# Lineboard.net
KiCad netlist of a schematic drawn in EAGLE
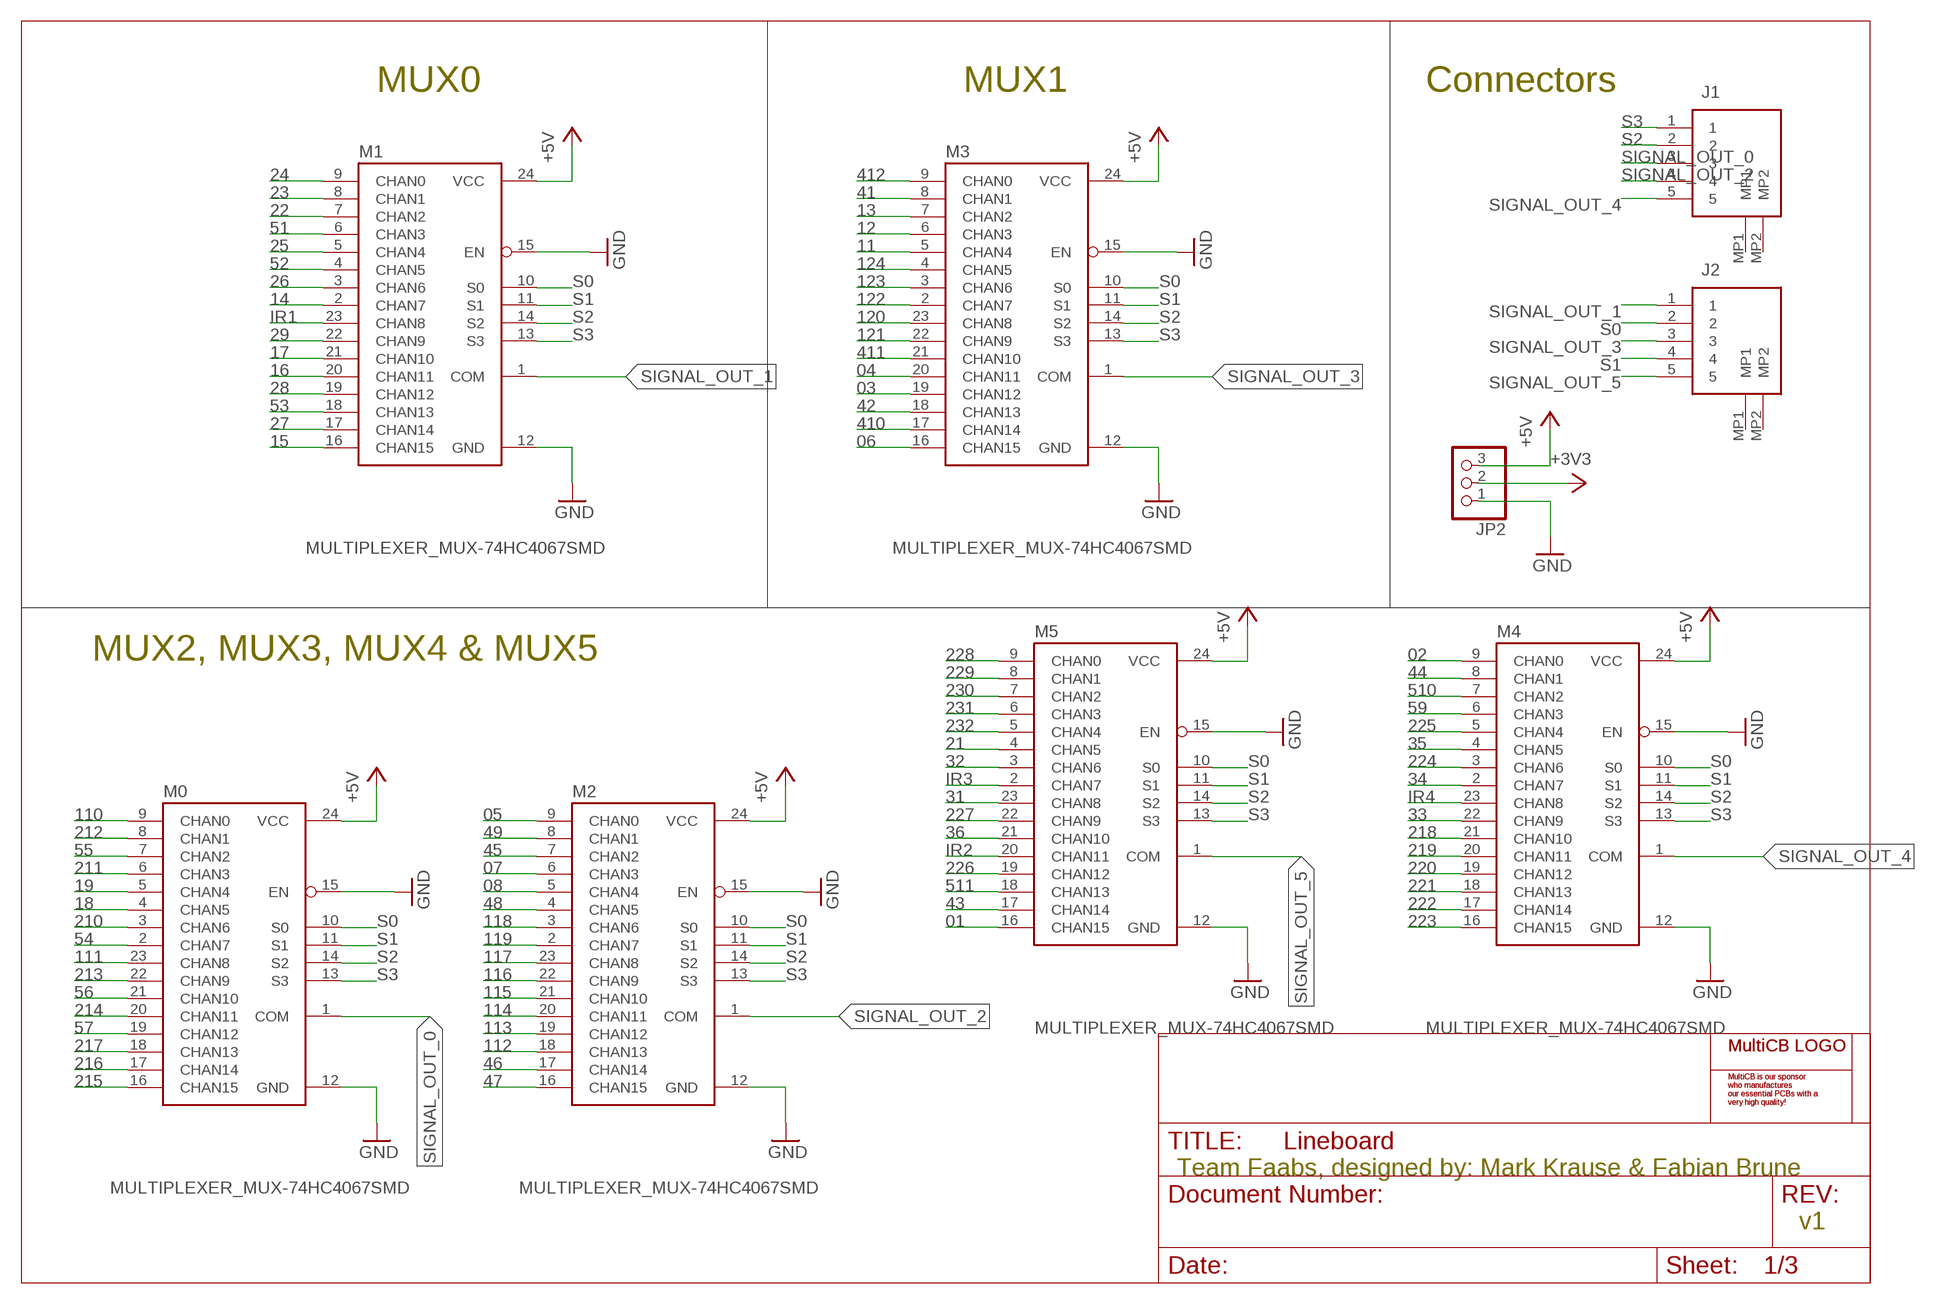
[diagram p0: schematic, sheet 1]
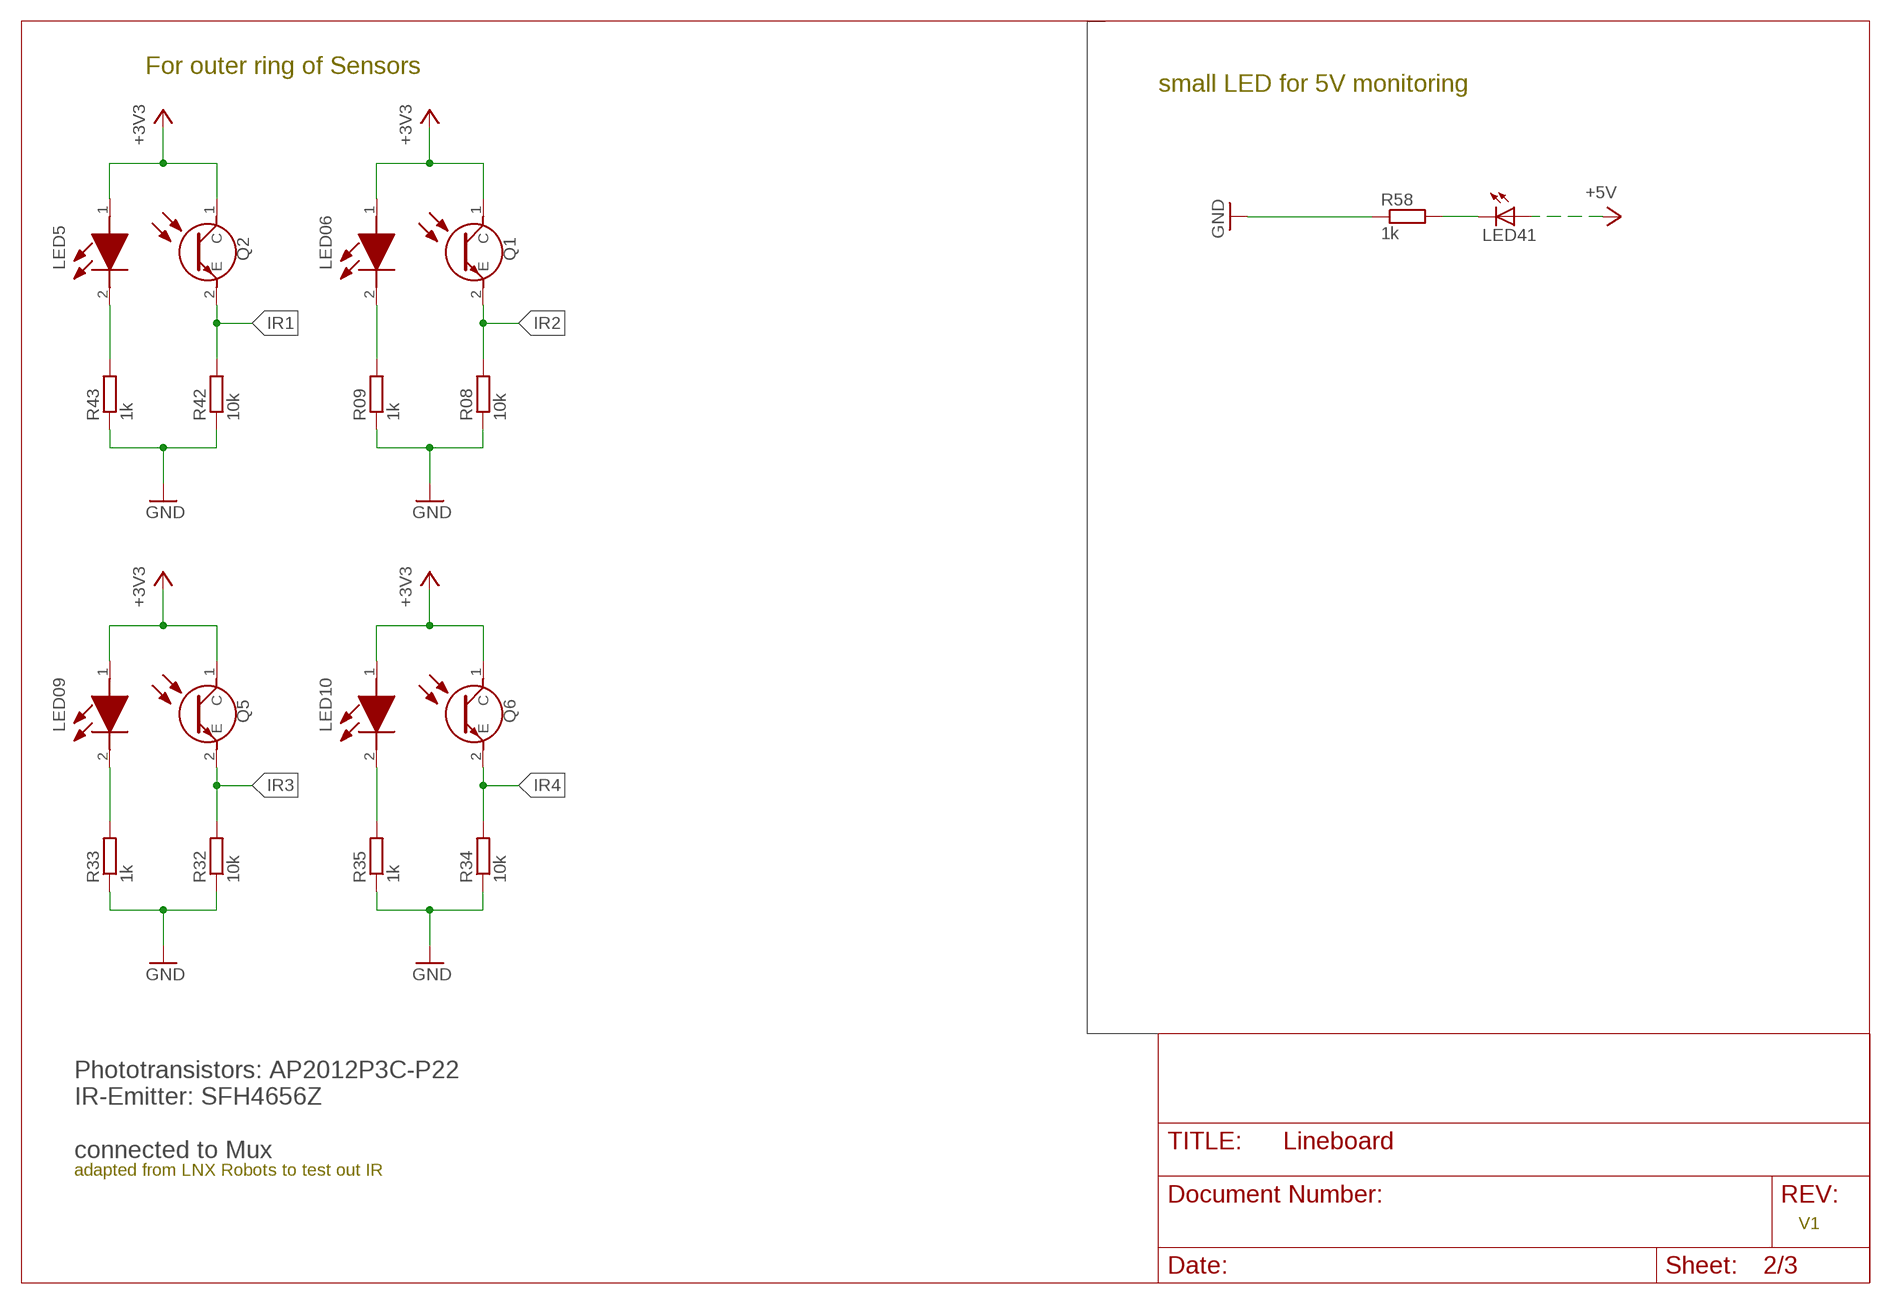
[diagram p1: schematic, sheet 2]
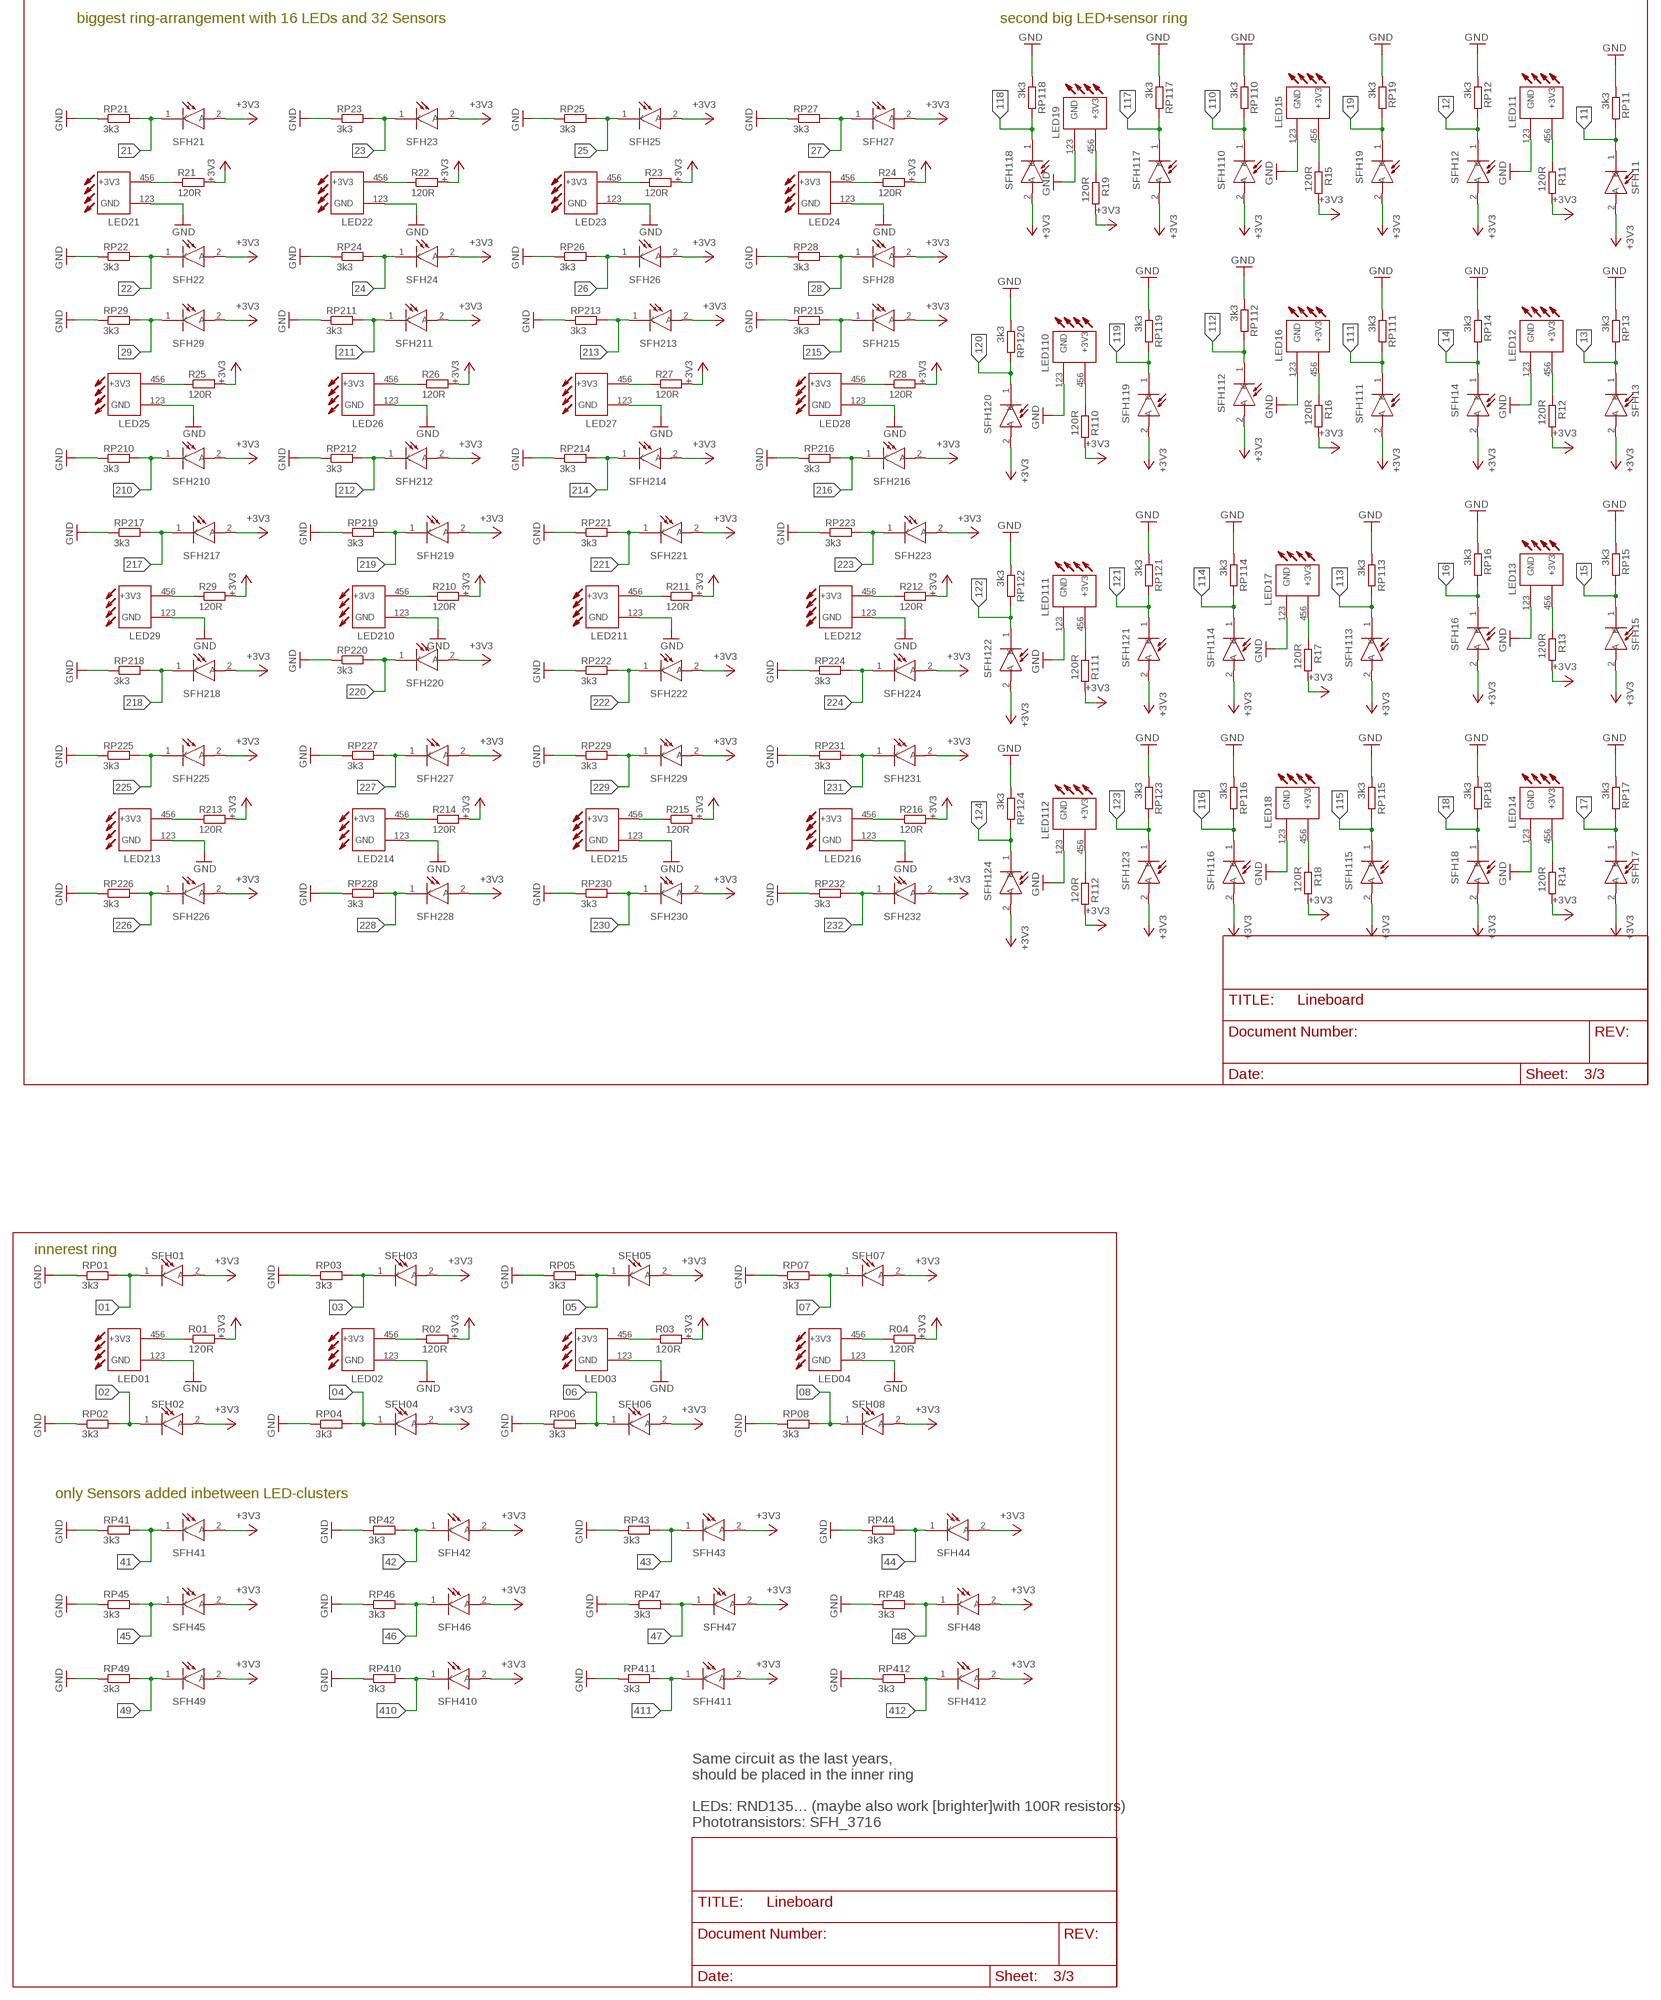
[diagram p2: schematic, sheet 3, part 1 of 2]
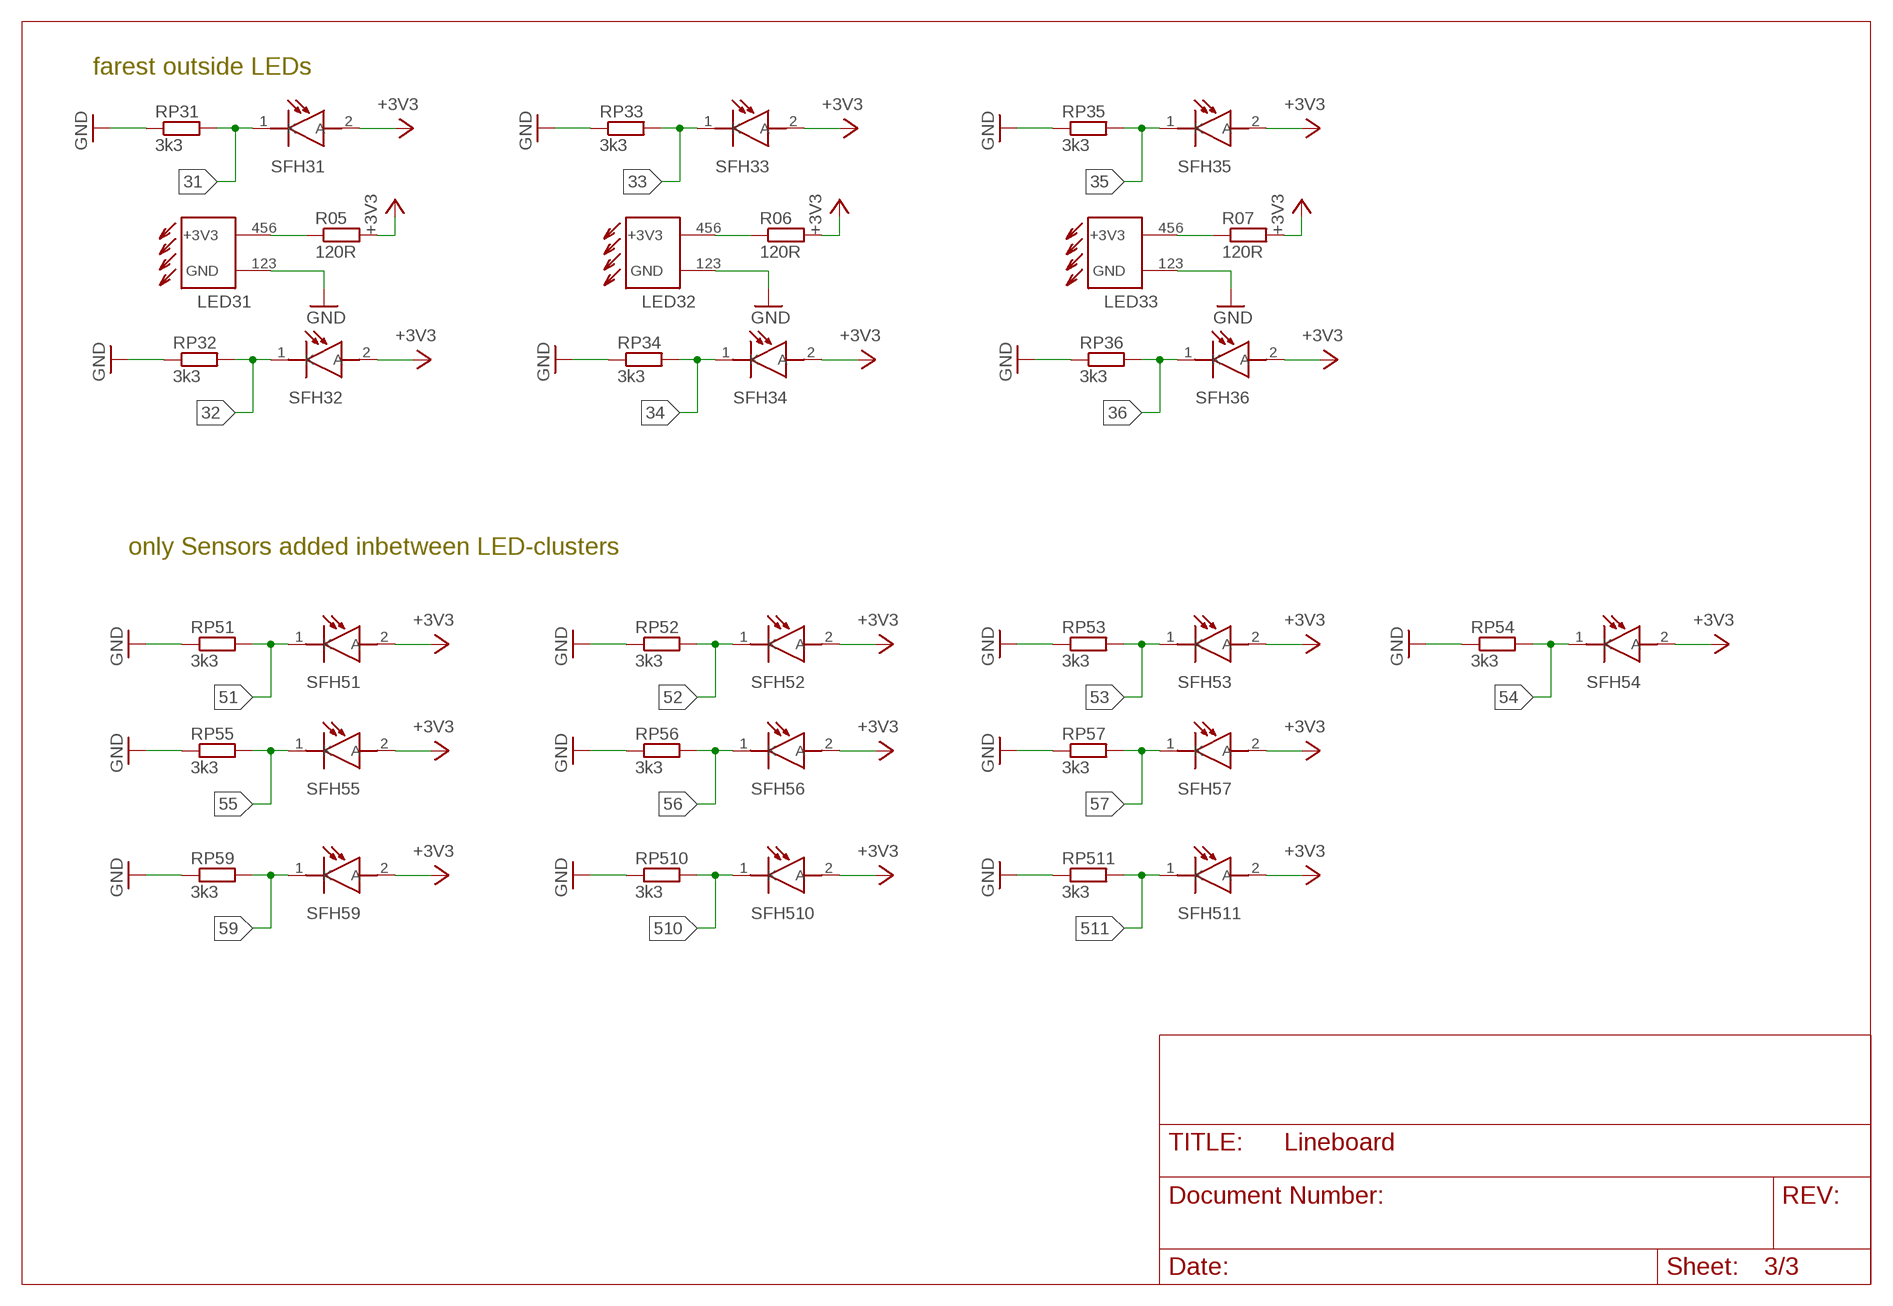
[diagram p3: schematic, sheet 3, part 2 of 2]

(export (version "E")
  (design (tool "Eeschema 10.0.6"))
  (components
    (comp (ref "J1")
      (value "5PIN_1MM_CON")
      (footprint "eagle-import:2035600503")
      (fields
        (field (name "MANUFACTURER_PART_NUMBER") "203560-0503")
        (field (name "MOUSER_PART_NUMBER") "538-203560-0503")
      )
      (libsource (lib "eagle-import") (part "5PIN_1MM_CON"))
    )
    (comp (ref "J2")
      (value "5PIN_1MM_CON")
      (footprint "eagle-import:2035600503")
      (fields
        (field (name "MANUFACTURER_PART_NUMBER") "203560-0503")
        (field (name "MOUSER_PART_NUMBER") "538-203560-0503")
      )
      (libsource (lib "eagle-import") (part "5PIN_1MM_CON"))
    )
    (comp (ref "JP2")
      (value "PINHD-1X3")
      (footprint "eagle-import:1X03")
      (libsource (lib "eagle-import") (part "PINHD-1X3"))
    )
    (comp (ref "M0")
      (value "MULTIPLEXER_MUX-74HC4067SMD")
      (footprint "eagle-import:SPARKFUN_SSOP24")
      (libsource (lib "eagle-import") (part "MULTIPLEXER_MUX-74HC4067SMD"))
    )
    (comp (ref "M1")
      (value "MULTIPLEXER_MUX-74HC4067SMD")
      (footprint "eagle-import:SPARKFUN_SSOP24")
      (libsource (lib "eagle-import") (part "MULTIPLEXER_MUX-74HC4067SMD"))
    )
    (comp (ref "M2")
      (value "MULTIPLEXER_MUX-74HC4067SMD")
      (footprint "eagle-import:SPARKFUN_SSOP24")
      (libsource (lib "eagle-import") (part "MULTIPLEXER_MUX-74HC4067SMD"))
    )
    (comp (ref "M3")
      (value "MULTIPLEXER_MUX-74HC4067SMD")
      (footprint "eagle-import:SPARKFUN_SSOP24")
      (libsource (lib "eagle-import") (part "MULTIPLEXER_MUX-74HC4067SMD"))
    )
    (comp (ref "M4")
      (value "MULTIPLEXER_MUX-74HC4067SMD")
      (footprint "eagle-import:SPARKFUN_SSOP24")
      (libsource (lib "eagle-import") (part "MULTIPLEXER_MUX-74HC4067SMD"))
    )
    (comp (ref "M5")
      (value "MULTIPLEXER_MUX-74HC4067SMD")
      (footprint "eagle-import:SPARKFUN_SSOP24")
      (libsource (lib "eagle-import") (part "MULTIPLEXER_MUX-74HC4067SMD"))
    )
    (comp (ref "U$1")
      (value "MULTICB_LOGOSTANDART")
      (footprint "eagle-import:SMALL_STANDARTLOGO_28MM")
      (libsource (lib "eagle-import") (part "MULTICB_LOGOSTANDART"))
    )
    (comp (ref "U$5")
      (value "MULTICB_LOGOSTANDART")
      (footprint "eagle-import:SMALL_STANDARTLOGO_28MM")
      (libsource (lib "eagle-import") (part "MULTICB_LOGOSTANDART"))
    )
    (comp (ref "LED01")
      (value "RND135-00056LEDD")
      (footprint "eagle-import:LED")
      (libsource (lib "eagle-import") (part "RND135-00056LEDD"))
    )
    (comp (ref "LED02")
      (value "RND135-00056LEDD")
      (footprint "eagle-import:LED")
      (libsource (lib "eagle-import") (part "RND135-00056LEDD"))
    )
    (comp (ref "LED03")
      (value "RND135-00056LEDD")
      (footprint "eagle-import:LED")
      (libsource (lib "eagle-import") (part "RND135-00056LEDD"))
    )
    (comp (ref "LED04")
      (value "RND135-00056LEDD")
      (footprint "eagle-import:LED")
      (libsource (lib "eagle-import") (part "RND135-00056LEDD"))
    )
    (comp (ref "LED11")
      (value "RND135-00056LEDD")
      (footprint "eagle-import:LED")
      (libsource (lib "eagle-import") (part "RND135-00056LEDD"))
    )
    (comp (ref "LED12")
      (value "RND135-00056LEDD")
      (footprint "eagle-import:LED")
      (libsource (lib "eagle-import") (part "RND135-00056LEDD"))
    )
    (comp (ref "LED13")
      (value "RND135-00056LEDD")
      (footprint "eagle-import:LED")
      (libsource (lib "eagle-import") (part "RND135-00056LEDD"))
    )
    (comp (ref "LED14")
      (value "RND135-00056LEDD")
      (footprint "eagle-import:LED")
      (libsource (lib "eagle-import") (part "RND135-00056LEDD"))
    )
    (comp (ref "LED15")
      (value "RND135-00056LEDD")
      (footprint "eagle-import:LED")
      (libsource (lib "eagle-import") (part "RND135-00056LEDD"))
    )
    (comp (ref "LED16")
      (value "RND135-00056LEDD")
      (footprint "eagle-import:LED")
      (libsource (lib "eagle-import") (part "RND135-00056LEDD"))
    )
    (comp (ref "LED17")
      (value "RND135-00056LEDD")
      (footprint "eagle-import:LED")
      (libsource (lib "eagle-import") (part "RND135-00056LEDD"))
    )
    (comp (ref "LED18")
      (value "RND135-00056LEDD")
      (footprint "eagle-import:LED")
      (libsource (lib "eagle-import") (part "RND135-00056LEDD"))
    )
    (comp (ref "LED19")
      (value "RND135-00056LEDD")
      (footprint "eagle-import:LED")
      (libsource (lib "eagle-import") (part "RND135-00056LEDD"))
    )
    (comp (ref "LED21")
      (value "RND135-00056LEDD")
      (footprint "eagle-import:LED")
      (libsource (lib "eagle-import") (part "RND135-00056LEDD"))
    )
    (comp (ref "LED22")
      (value "RND135-00056LEDD")
      (footprint "eagle-import:LED")
      (libsource (lib "eagle-import") (part "RND135-00056LEDD"))
    )
    (comp (ref "LED23")
      (value "RND135-00056LEDD")
      (footprint "eagle-import:LED")
      (libsource (lib "eagle-import") (part "RND135-00056LEDD"))
    )
    (comp (ref "LED24")
      (value "RND135-00056LEDD")
      (footprint "eagle-import:LED")
      (libsource (lib "eagle-import") (part "RND135-00056LEDD"))
    )
    (comp (ref "LED25")
      (value "RND135-00056LEDD")
      (footprint "eagle-import:LED")
      (libsource (lib "eagle-import") (part "RND135-00056LEDD"))
    )
    (comp (ref "LED26")
      (value "RND135-00056LEDD")
      (footprint "eagle-import:LED")
      (libsource (lib "eagle-import") (part "RND135-00056LEDD"))
    )
    (comp (ref "LED27")
      (value "RND135-00056LEDD")
      (footprint "eagle-import:LED")
      (libsource (lib "eagle-import") (part "RND135-00056LEDD"))
    )
    (comp (ref "LED28")
      (value "RND135-00056LEDD")
      (footprint "eagle-import:LED")
      (libsource (lib "eagle-import") (part "RND135-00056LEDD"))
    )
    (comp (ref "LED29")
      (value "RND135-00056LEDD")
      (footprint "eagle-import:LED")
      (libsource (lib "eagle-import") (part "RND135-00056LEDD"))
    )
    (comp (ref "LED31")
      (value "RND135-00056LEDD")
      (footprint "eagle-import:LED")
      (libsource (lib "eagle-import") (part "RND135-00056LEDD"))
    )
    (comp (ref "LED32")
      (value "RND135-00056LEDD")
      (footprint "eagle-import:LED")
      (libsource (lib "eagle-import") (part "RND135-00056LEDD"))
    )
    (comp (ref "LED33")
      (value "RND135-00056LEDD")
      (footprint "eagle-import:LED")
      (libsource (lib "eagle-import") (part "RND135-00056LEDD"))
    )
    (comp (ref "LED110")
      (value "RND135-00056LEDD")
      (footprint "eagle-import:LED")
      (libsource (lib "eagle-import") (part "RND135-00056LEDD"))
    )
    (comp (ref "LED111")
      (value "RND135-00056LEDD")
      (footprint "eagle-import:LED")
      (libsource (lib "eagle-import") (part "RND135-00056LEDD"))
    )
    (comp (ref "LED112")
      (value "RND135-00056LEDD")
      (footprint "eagle-import:LED")
      (libsource (lib "eagle-import") (part "RND135-00056LEDD"))
    )
    (comp (ref "LED210")
      (value "RND135-00056LEDD")
      (footprint "eagle-import:LED")
      (libsource (lib "eagle-import") (part "RND135-00056LEDD"))
    )
    (comp (ref "LED211")
      (value "RND135-00056LEDD")
      (footprint "eagle-import:LED")
      (libsource (lib "eagle-import") (part "RND135-00056LEDD"))
    )
    (comp (ref "LED212")
      (value "RND135-00056LEDD")
      (footprint "eagle-import:LED")
      (libsource (lib "eagle-import") (part "RND135-00056LEDD"))
    )
    (comp (ref "LED213")
      (value "RND135-00056LEDD")
      (footprint "eagle-import:LED")
      (libsource (lib "eagle-import") (part "RND135-00056LEDD"))
    )
    (comp (ref "LED214")
      (value "RND135-00056LEDD")
      (footprint "eagle-import:LED")
      (libsource (lib "eagle-import") (part "RND135-00056LEDD"))
    )
    (comp (ref "LED215")
      (value "RND135-00056LEDD")
      (footprint "eagle-import:LED")
      (libsource (lib "eagle-import") (part "RND135-00056LEDD"))
    )
    (comp (ref "LED216")
      (value "RND135-00056LEDD")
      (footprint "eagle-import:LED")
      (libsource (lib "eagle-import") (part "RND135-00056LEDD"))
    )
    (comp (ref "R01")
      (value "120R")
      (footprint "eagle-import:R0603")
      (libsource (lib "eagle-import") (part "R-EU_R0603"))
    )
    (comp (ref "R02")
      (value "120R")
      (footprint "eagle-import:R0603")
      (libsource (lib "eagle-import") (part "R-EU_R0603"))
    )
    (comp (ref "R03")
      (value "120R")
      (footprint "eagle-import:R0603")
      (libsource (lib "eagle-import") (part "R-EU_R0603"))
    )
    (comp (ref "R04")
      (value "120R")
      (footprint "eagle-import:R0603")
      (libsource (lib "eagle-import") (part "R-EU_R0603"))
    )
    (comp (ref "R05")
      (value "120R")
      (footprint "eagle-import:R0603")
      (libsource (lib "eagle-import") (part "R-EU_R0603"))
    )
    (comp (ref "R06")
      (value "120R")
      (footprint "eagle-import:R0603")
      (libsource (lib "eagle-import") (part "R-EU_R0603"))
    )
    (comp (ref "R07")
      (value "120R")
      (footprint "eagle-import:R0603")
      (libsource (lib "eagle-import") (part "R-EU_R0603"))
    )
    (comp (ref "R11")
      (value "120R")
      (footprint "eagle-import:R0603")
      (libsource (lib "eagle-import") (part "R-EU_R0603"))
    )
    (comp (ref "R12")
      (value "120R")
      (footprint "eagle-import:R0603")
      (libsource (lib "eagle-import") (part "R-EU_R0603"))
    )
    (comp (ref "R13")
      (value "120R")
      (footprint "eagle-import:R0603")
      (libsource (lib "eagle-import") (part "R-EU_R0603"))
    )
    (comp (ref "R14")
      (value "120R")
      (footprint "eagle-import:R0603")
      (libsource (lib "eagle-import") (part "R-EU_R0603"))
    )
    (comp (ref "R15")
      (value "120R")
      (footprint "eagle-import:R0603")
      (libsource (lib "eagle-import") (part "R-EU_R0603"))
    )
    (comp (ref "R16")
      (value "120R")
      (footprint "eagle-import:R0603")
      (libsource (lib "eagle-import") (part "R-EU_R0603"))
    )
    (comp (ref "R17")
      (value "120R")
      (footprint "eagle-import:R0603")
      (libsource (lib "eagle-import") (part "R-EU_R0603"))
    )
    (comp (ref "R18")
      (value "120R")
      (footprint "eagle-import:R0603")
      (libsource (lib "eagle-import") (part "R-EU_R0603"))
    )
    (comp (ref "R19")
      (value "120R")
      (footprint "eagle-import:R0603")
      (libsource (lib "eagle-import") (part "R-EU_R0603"))
    )
    (comp (ref "R21")
      (value "120R")
      (footprint "eagle-import:R0603")
      (libsource (lib "eagle-import") (part "R-EU_R0603"))
    )
    (comp (ref "R22")
      (value "120R")
      (footprint "eagle-import:R0603")
      (libsource (lib "eagle-import") (part "R-EU_R0603"))
    )
    (comp (ref "R23")
      (value "120R")
      (footprint "eagle-import:R0603")
      (libsource (lib "eagle-import") (part "R-EU_R0603"))
    )
    (comp (ref "R24")
      (value "120R")
      (footprint "eagle-import:R0603")
      (libsource (lib "eagle-import") (part "R-EU_R0603"))
    )
    (comp (ref "R25")
      (value "120R")
      (footprint "eagle-import:R0603")
      (libsource (lib "eagle-import") (part "R-EU_R0603"))
    )
    (comp (ref "R26")
      (value "120R")
      (footprint "eagle-import:R0603")
      (libsource (lib "eagle-import") (part "R-EU_R0603"))
    )
    (comp (ref "R27")
      (value "120R")
      (footprint "eagle-import:R0603")
      (libsource (lib "eagle-import") (part "R-EU_R0603"))
    )
    (comp (ref "R28")
      (value "120R")
      (footprint "eagle-import:R0603")
      (libsource (lib "eagle-import") (part "R-EU_R0603"))
    )
    (comp (ref "R29")
      (value "120R")
      (footprint "eagle-import:R0603")
      (libsource (lib "eagle-import") (part "R-EU_R0603"))
    )
    (comp (ref "R110")
      (value "120R")
      (footprint "eagle-import:R0603")
      (libsource (lib "eagle-import") (part "R-EU_R0603"))
    )
    (comp (ref "R111")
      (value "120R")
      (footprint "eagle-import:R0603")
      (libsource (lib "eagle-import") (part "R-EU_R0603"))
    )
    (comp (ref "R112")
      (value "120R")
      (footprint "eagle-import:R0603")
      (libsource (lib "eagle-import") (part "R-EU_R0603"))
    )
    (comp (ref "R210")
      (value "120R")
      (footprint "eagle-import:R0603")
      (libsource (lib "eagle-import") (part "R-EU_R0603"))
    )
    (comp (ref "R211")
      (value "120R")
      (footprint "eagle-import:R0603")
      (libsource (lib "eagle-import") (part "R-EU_R0603"))
    )
    (comp (ref "R212")
      (value "120R")
      (footprint "eagle-import:R0603")
      (libsource (lib "eagle-import") (part "R-EU_R0603"))
    )
    (comp (ref "R213")
      (value "120R")
      (footprint "eagle-import:R0603")
      (libsource (lib "eagle-import") (part "R-EU_R0603"))
    )
    (comp (ref "R214")
      (value "120R")
      (footprint "eagle-import:R0603")
      (libsource (lib "eagle-import") (part "R-EU_R0603"))
    )
    (comp (ref "R215")
      (value "120R")
      (footprint "eagle-import:R0603")
      (libsource (lib "eagle-import") (part "R-EU_R0603"))
    )
    (comp (ref "R216")
      (value "120R")
      (footprint "eagle-import:R0603")
      (libsource (lib "eagle-import") (part "R-EU_R0603"))
    )
    (comp (ref "RP01")
      (value "3k3")
      (footprint "eagle-import:R0603")
      (libsource (lib "eagle-import") (part "R-EU_R0603"))
    )
    (comp (ref "RP02")
      (value "3k3")
      (footprint "eagle-import:R0603")
      (libsource (lib "eagle-import") (part "R-EU_R0603"))
    )
    (comp (ref "RP03")
      (value "3k3")
      (footprint "eagle-import:R0603")
      (libsource (lib "eagle-import") (part "R-EU_R0603"))
    )
    (comp (ref "RP04")
      (value "3k3")
      (footprint "eagle-import:R0603")
      (libsource (lib "eagle-import") (part "R-EU_R0603"))
    )
    (comp (ref "RP05")
      (value "3k3")
      (footprint "eagle-import:R0603")
      (libsource (lib "eagle-import") (part "R-EU_R0603"))
    )
    (comp (ref "RP06")
      (value "3k3")
      (footprint "eagle-import:R0603")
      (libsource (lib "eagle-import") (part "R-EU_R0603"))
    )
    (comp (ref "RP07")
      (value "3k3")
      (footprint "eagle-import:R0603")
      (libsource (lib "eagle-import") (part "R-EU_R0603"))
    )
    (comp (ref "RP08")
      (value "3k3")
      (footprint "eagle-import:R0603")
      (libsource (lib "eagle-import") (part "R-EU_R0603"))
    )
    (comp (ref "RP11")
      (value "3k3")
      (footprint "eagle-import:R0603")
      (libsource (lib "eagle-import") (part "R-EU_R0603"))
    )
    (comp (ref "RP12")
      (value "3k3")
      (footprint "eagle-import:R0603")
      (libsource (lib "eagle-import") (part "R-EU_R0603"))
    )
    (comp (ref "RP13")
      (value "3k3")
      (footprint "eagle-import:R0603")
      (libsource (lib "eagle-import") (part "R-EU_R0603"))
    )
    (comp (ref "RP14")
      (value "3k3")
      (footprint "eagle-import:R0603")
      (libsource (lib "eagle-import") (part "R-EU_R0603"))
    )
    (comp (ref "RP15")
      (value "3k3")
      (footprint "eagle-import:R0603")
      (libsource (lib "eagle-import") (part "R-EU_R0603"))
    )
    (comp (ref "RP16")
      (value "3k3")
      (footprint "eagle-import:R0603")
      (libsource (lib "eagle-import") (part "R-EU_R0603"))
    )
    (comp (ref "RP17")
      (value "3k3")
      (footprint "eagle-import:R0603")
      (libsource (lib "eagle-import") (part "R-EU_R0603"))
    )
    (comp (ref "RP18")
      (value "3k3")
      (footprint "eagle-import:R0603")
      (libsource (lib "eagle-import") (part "R-EU_R0603"))
    )
    (comp (ref "RP19")
      (value "3k3")
      (footprint "eagle-import:R0603")
      (libsource (lib "eagle-import") (part "R-EU_R0603"))
    )
    (comp (ref "RP21")
      (value "3k3")
      (footprint "eagle-import:R0603")
      (libsource (lib "eagle-import") (part "R-EU_R0603"))
    )
    (comp (ref "RP22")
      (value "3k3")
      (footprint "eagle-import:R0603")
      (libsource (lib "eagle-import") (part "R-EU_R0603"))
    )
    (comp (ref "RP23")
      (value "3k3")
      (footprint "eagle-import:R0603")
      (libsource (lib "eagle-import") (part "R-EU_R0603"))
    )
    (comp (ref "RP24")
      (value "3k3")
      (footprint "eagle-import:R0603")
      (libsource (lib "eagle-import") (part "R-EU_R0603"))
    )
    (comp (ref "RP25")
      (value "3k3")
      (footprint "eagle-import:R0603")
      (libsource (lib "eagle-import") (part "R-EU_R0603"))
    )
    (comp (ref "RP26")
      (value "3k3")
      (footprint "eagle-import:R0603")
      (libsource (lib "eagle-import") (part "R-EU_R0603"))
    )
    (comp (ref "RP27")
      (value "3k3")
      (footprint "eagle-import:R0603")
      (libsource (lib "eagle-import") (part "R-EU_R0603"))
    )
    (comp (ref "RP28")
      (value "3k3")
      (footprint "eagle-import:R0603")
      (libsource (lib "eagle-import") (part "R-EU_R0603"))
    )
    (comp (ref "RP29")
      (value "3k3")
      (footprint "eagle-import:R0603")
      (libsource (lib "eagle-import") (part "R-EU_R0603"))
    )
    (comp (ref "RP31")
      (value "3k3")
      (footprint "eagle-import:R0603")
      (libsource (lib "eagle-import") (part "R-EU_R0603"))
    )
    (comp (ref "RP32")
      (value "3k3")
      (footprint "eagle-import:R0603")
      (libsource (lib "eagle-import") (part "R-EU_R0603"))
    )
    (comp (ref "RP33")
      (value "3k3")
      (footprint "eagle-import:R0603")
      (libsource (lib "eagle-import") (part "R-EU_R0603"))
    )
    (comp (ref "RP34")
      (value "3k3")
      (footprint "eagle-import:R0603")
      (libsource (lib "eagle-import") (part "R-EU_R0603"))
    )
    (comp (ref "RP35")
      (value "3k3")
      (footprint "eagle-import:R0603")
      (libsource (lib "eagle-import") (part "R-EU_R0603"))
    )
    (comp (ref "RP36")
      (value "3k3")
      (footprint "eagle-import:R0603")
      (libsource (lib "eagle-import") (part "R-EU_R0603"))
    )
    (comp (ref "RP41")
      (value "3k3")
      (footprint "eagle-import:R0603")
      (libsource (lib "eagle-import") (part "R-EU_R0603"))
    )
    (comp (ref "RP42")
      (value "3k3")
      (footprint "eagle-import:R0603")
      (libsource (lib "eagle-import") (part "R-EU_R0603"))
    )
    (comp (ref "RP43")
      (value "3k3")
      (footprint "eagle-import:R0603")
      (libsource (lib "eagle-import") (part "R-EU_R0603"))
    )
    (comp (ref "RP44")
      (value "3k3")
      (footprint "eagle-import:R0603")
      (libsource (lib "eagle-import") (part "R-EU_R0603"))
    )
    (comp (ref "RP45")
      (value "3k3")
      (footprint "eagle-import:R0603")
      (libsource (lib "eagle-import") (part "R-EU_R0603"))
    )
    (comp (ref "RP46")
      (value "3k3")
      (footprint "eagle-import:R0603")
      (libsource (lib "eagle-import") (part "R-EU_R0603"))
    )
    (comp (ref "RP47")
      (value "3k3")
      (footprint "eagle-import:R0603")
      (libsource (lib "eagle-import") (part "R-EU_R0603"))
    )
    (comp (ref "RP48")
      (value "3k3")
      (footprint "eagle-import:R0603")
      (libsource (lib "eagle-import") (part "R-EU_R0603"))
    )
    (comp (ref "RP49")
      (value "3k3")
      (footprint "eagle-import:R0603")
      (libsource (lib "eagle-import") (part "R-EU_R0603"))
    )
    (comp (ref "RP51")
      (value "3k3")
      (footprint "eagle-import:R0603")
      (libsource (lib "eagle-import") (part "R-EU_R0603"))
    )
    (comp (ref "RP52")
      (value "3k3")
      (footprint "eagle-import:R0603")
      (libsource (lib "eagle-import") (part "R-EU_R0603"))
    )
    (comp (ref "RP53")
      (value "3k3")
      (footprint "eagle-import:R0603")
      (libsource (lib "eagle-import") (part "R-EU_R0603"))
    )
    (comp (ref "RP54")
      (value "3k3")
      (footprint "eagle-import:R0603")
      (libsource (lib "eagle-import") (part "R-EU_R0603"))
    )
    (comp (ref "RP55")
      (value "3k3")
      (footprint "eagle-import:R0603")
      (libsource (lib "eagle-import") (part "R-EU_R0603"))
    )
    (comp (ref "RP56")
      (value "3k3")
      (footprint "eagle-import:R0603")
      (libsource (lib "eagle-import") (part "R-EU_R0603"))
    )
    (comp (ref "RP57")
      (value "3k3")
      (footprint "eagle-import:R0603")
      (libsource (lib "eagle-import") (part "R-EU_R0603"))
    )
    (comp (ref "RP59")
      (value "3k3")
      (footprint "eagle-import:R0603")
      (libsource (lib "eagle-import") (part "R-EU_R0603"))
    )
    (comp (ref "RP110")
      (value "3k3")
      (footprint "eagle-import:R0603")
      (libsource (lib "eagle-import") (part "R-EU_R0603"))
    )
    (comp (ref "RP111")
      (value "3k3")
      (footprint "eagle-import:R0603")
      (libsource (lib "eagle-import") (part "R-EU_R0603"))
    )
    (comp (ref "RP112")
      (value "3k3")
      (footprint "eagle-import:R0603")
      (libsource (lib "eagle-import") (part "R-EU_R0603"))
    )
    (comp (ref "RP113")
      (value "3k3")
      (footprint "eagle-import:R0603")
      (libsource (lib "eagle-import") (part "R-EU_R0603"))
    )
    (comp (ref "RP114")
      (value "3k3")
      (footprint "eagle-import:R0603")
      (libsource (lib "eagle-import") (part "R-EU_R0603"))
    )
    (comp (ref "RP115")
      (value "3k3")
      (footprint "eagle-import:R0603")
      (libsource (lib "eagle-import") (part "R-EU_R0603"))
    )
    (comp (ref "RP116")
      (value "3k3")
      (footprint "eagle-import:R0603")
      (libsource (lib "eagle-import") (part "R-EU_R0603"))
    )
    (comp (ref "RP117")
      (value "3k3")
      (footprint "eagle-import:R0603")
      (libsource (lib "eagle-import") (part "R-EU_R0603"))
    )
    (comp (ref "RP118")
      (value "3k3")
      (footprint "eagle-import:R0603")
      (libsource (lib "eagle-import") (part "R-EU_R0603"))
    )
    (comp (ref "RP119")
      (value "3k3")
      (footprint "eagle-import:R0603")
      (libsource (lib "eagle-import") (part "R-EU_R0603"))
    )
    (comp (ref "RP120")
      (value "3k3")
      (footprint "eagle-import:R0603")
      (libsource (lib "eagle-import") (part "R-EU_R0603"))
    )
    (comp (ref "RP121")
      (value "3k3")
      (footprint "eagle-import:R0603")
      (libsource (lib "eagle-import") (part "R-EU_R0603"))
    )
    (comp (ref "RP122")
      (value "3k3")
      (footprint "eagle-import:R0603")
      (libsource (lib "eagle-import") (part "R-EU_R0603"))
    )
    (comp (ref "RP123")
      (value "3k3")
      (footprint "eagle-import:R0603")
      (libsource (lib "eagle-import") (part "R-EU_R0603"))
    )
    (comp (ref "RP124")
      (value "3k3")
      (footprint "eagle-import:R0603")
      (libsource (lib "eagle-import") (part "R-EU_R0603"))
    )
    (comp (ref "RP210")
      (value "3k3")
      (footprint "eagle-import:R0603")
      (libsource (lib "eagle-import") (part "R-EU_R0603"))
    )
    (comp (ref "RP211")
      (value "3k3")
      (footprint "eagle-import:R0603")
      (libsource (lib "eagle-import") (part "R-EU_R0603"))
    )
    (comp (ref "RP212")
      (value "3k3")
      (footprint "eagle-import:R0603")
      (libsource (lib "eagle-import") (part "R-EU_R0603"))
    )
    (comp (ref "RP213")
      (value "3k3")
      (footprint "eagle-import:R0603")
      (libsource (lib "eagle-import") (part "R-EU_R0603"))
    )
    (comp (ref "RP214")
      (value "3k3")
      (footprint "eagle-import:R0603")
      (libsource (lib "eagle-import") (part "R-EU_R0603"))
    )
    (comp (ref "RP215")
      (value "3k3")
      (footprint "eagle-import:R0603")
      (libsource (lib "eagle-import") (part "R-EU_R0603"))
    )
    (comp (ref "RP216")
      (value "3k3")
      (footprint "eagle-import:R0603")
      (libsource (lib "eagle-import") (part "R-EU_R0603"))
    )
    (comp (ref "RP217")
      (value "3k3")
      (footprint "eagle-import:R0603")
      (libsource (lib "eagle-import") (part "R-EU_R0603"))
    )
    (comp (ref "RP218")
      (value "3k3")
      (footprint "eagle-import:R0603")
      (libsource (lib "eagle-import") (part "R-EU_R0603"))
    )
    (comp (ref "RP219")
      (value "3k3")
      (footprint "eagle-import:R0603")
      (libsource (lib "eagle-import") (part "R-EU_R0603"))
    )
    (comp (ref "RP220")
      (value "3k3")
      (footprint "eagle-import:R0603")
      (libsource (lib "eagle-import") (part "R-EU_R0603"))
    )
    (comp (ref "RP221")
      (value "3k3")
      (footprint "eagle-import:R0603")
      (libsource (lib "eagle-import") (part "R-EU_R0603"))
    )
    (comp (ref "RP222")
      (value "3k3")
      (footprint "eagle-import:R0603")
      (libsource (lib "eagle-import") (part "R-EU_R0603"))
    )
    (comp (ref "RP223")
      (value "3k3")
      (footprint "eagle-import:R0603")
      (libsource (lib "eagle-import") (part "R-EU_R0603"))
    )
    (comp (ref "RP224")
      (value "3k3")
      (footprint "eagle-import:R0603")
      (libsource (lib "eagle-import") (part "R-EU_R0603"))
    )
    (comp (ref "RP225")
      (value "3k3")
      (footprint "eagle-import:R0603")
      (libsource (lib "eagle-import") (part "R-EU_R0603"))
    )
    (comp (ref "RP226")
      (value "3k3")
      (footprint "eagle-import:R0603")
      (libsource (lib "eagle-import") (part "R-EU_R0603"))
    )
    (comp (ref "RP227")
      (value "3k3")
      (footprint "eagle-import:R0603")
      (libsource (lib "eagle-import") (part "R-EU_R0603"))
    )
    (comp (ref "RP228")
      (value "3k3")
      (footprint "eagle-import:R0603")
      (libsource (lib "eagle-import") (part "R-EU_R0603"))
    )
    (comp (ref "RP229")
      (value "3k3")
      (footprint "eagle-import:R0603")
      (libsource (lib "eagle-import") (part "R-EU_R0603"))
    )
    (comp (ref "RP230")
      (value "3k3")
      (footprint "eagle-import:R0603")
      (libsource (lib "eagle-import") (part "R-EU_R0603"))
    )
    (comp (ref "RP231")
      (value "3k3")
      (footprint "eagle-import:R0603")
      (libsource (lib "eagle-import") (part "R-EU_R0603"))
    )
    (comp (ref "RP232")
      (value "3k3")
      (footprint "eagle-import:R0603")
      (libsource (lib "eagle-import") (part "R-EU_R0603"))
    )
    (comp (ref "RP410")
      (value "3k3")
      (footprint "eagle-import:R0603")
      (libsource (lib "eagle-import") (part "R-EU_R0603"))
    )
    (comp (ref "RP411")
      (value "3k3")
      (footprint "eagle-import:R0603")
      (libsource (lib "eagle-import") (part "R-EU_R0603"))
    )
    (comp (ref "RP412")
      (value "3k3")
      (footprint "eagle-import:R0603")
      (libsource (lib "eagle-import") (part "R-EU_R0603"))
    )
    (comp (ref "RP510")
      (value "3k3")
      (footprint "eagle-import:R0603")
      (libsource (lib "eagle-import") (part "R-EU_R0603"))
    )
    (comp (ref "RP511")
      (value "3k3")
      (footprint "eagle-import:R0603")
      (libsource (lib "eagle-import") (part "R-EU_R0603"))
    )
    (comp (ref "SFH01")
      (value "SFH_3716")
      (footprint "eagle-import:LEDC2012X89N")
      (fields
        (field (name "MANUFACTURER_PART_NUMBER") "SFH 3716")
        (field (name "MOUSER_PART_NUMBER") "720-SFH3716")
        (field (name "RS_PART_NUMBER") "1115952P")
      )
      (libsource (lib "eagle-import") (part "SFH_3716"))
    )
    (comp (ref "SFH02")
      (value "SFH_3716")
      (footprint "eagle-import:LEDC2012X89N")
      (fields
        (field (name "MANUFACTURER_PART_NUMBER") "SFH 3716")
        (field (name "MOUSER_PART_NUMBER") "720-SFH3716")
        (field (name "RS_PART_NUMBER") "1115952P")
      )
      (libsource (lib "eagle-import") (part "SFH_3716"))
    )
    (comp (ref "SFH03")
      (value "SFH_3716")
      (footprint "eagle-import:LEDC2012X89N")
      (fields
        (field (name "MANUFACTURER_PART_NUMBER") "SFH 3716")
        (field (name "MOUSER_PART_NUMBER") "720-SFH3716")
        (field (name "RS_PART_NUMBER") "1115952P")
      )
      (libsource (lib "eagle-import") (part "SFH_3716"))
    )
    (comp (ref "SFH04")
      (value "SFH_3716")
      (footprint "eagle-import:LEDC2012X89N")
      (fields
        (field (name "MANUFACTURER_PART_NUMBER") "SFH 3716")
        (field (name "MOUSER_PART_NUMBER") "720-SFH3716")
        (field (name "RS_PART_NUMBER") "1115952P")
      )
      (libsource (lib "eagle-import") (part "SFH_3716"))
    )
    (comp (ref "SFH05")
      (value "SFH_3716")
      (footprint "eagle-import:LEDC2012X89N")
      (fields
        (field (name "MANUFACTURER_PART_NUMBER") "SFH 3716")
        (field (name "MOUSER_PART_NUMBER") "720-SFH3716")
        (field (name "RS_PART_NUMBER") "1115952P")
      )
      (libsource (lib "eagle-import") (part "SFH_3716"))
    )
    (comp (ref "SFH06")
      (value "SFH_3716")
      (footprint "eagle-import:LEDC2012X89N")
      (fields
        (field (name "MANUFACTURER_PART_NUMBER") "SFH 3716")
        (field (name "MOUSER_PART_NUMBER") "720-SFH3716")
        (field (name "RS_PART_NUMBER") "1115952P")
      )
      (libsource (lib "eagle-import") (part "SFH_3716"))
    )
    (comp (ref "SFH07")
      (value "SFH_3716")
      (footprint "eagle-import:LEDC2012X89N")
      (fields
        (field (name "MANUFACTURER_PART_NUMBER") "SFH 3716")
        (field (name "MOUSER_PART_NUMBER") "720-SFH3716")
        (field (name "RS_PART_NUMBER") "1115952P")
      )
      (libsource (lib "eagle-import") (part "SFH_3716"))
    )
    (comp (ref "SFH08")
      (value "SFH_3716")
      (footprint "eagle-import:LEDC2012X89N")
      (fields
        (field (name "MANUFACTURER_PART_NUMBER") "SFH 3716")
        (field (name "MOUSER_PART_NUMBER") "720-SFH3716")
        (field (name "RS_PART_NUMBER") "1115952P")
      )
      (libsource (lib "eagle-import") (part "SFH_3716"))
    )
    (comp (ref "SFH11")
      (value "SFH_3716")
      (footprint "eagle-import:LEDC2012X89N")
      (fields
        (field (name "MANUFACTURER_PART_NUMBER") "SFH 3716")
        (field (name "MOUSER_PART_NUMBER") "720-SFH3716")
        (field (name "RS_PART_NUMBER") "1115952P")
      )
      (libsource (lib "eagle-import") (part "SFH_3716"))
    )
    (comp (ref "SFH12")
      (value "SFH_3716")
      (footprint "eagle-import:LEDC2012X89N")
      (fields
        (field (name "MANUFACTURER_PART_NUMBER") "SFH 3716")
        (field (name "MOUSER_PART_NUMBER") "720-SFH3716")
        (field (name "RS_PART_NUMBER") "1115952P")
      )
      (libsource (lib "eagle-import") (part "SFH_3716"))
    )
    (comp (ref "SFH13")
      (value "SFH_3716")
      (footprint "eagle-import:LEDC2012X89N")
      (fields
        (field (name "MANUFACTURER_PART_NUMBER") "SFH 3716")
        (field (name "MOUSER_PART_NUMBER") "720-SFH3716")
        (field (name "RS_PART_NUMBER") "1115952P")
      )
      (libsource (lib "eagle-import") (part "SFH_3716"))
    )
    (comp (ref "SFH14")
      (value "SFH_3716")
      (footprint "eagle-import:LEDC2012X89N")
      (fields
        (field (name "MANUFACTURER_PART_NUMBER") "SFH 3716")
        (field (name "MOUSER_PART_NUMBER") "720-SFH3716")
        (field (name "RS_PART_NUMBER") "1115952P")
      )
      (libsource (lib "eagle-import") (part "SFH_3716"))
    )
    (comp (ref "SFH15")
      (value "SFH_3716")
      (footprint "eagle-import:LEDC2012X89N")
      (fields
        (field (name "MANUFACTURER_PART_NUMBER") "SFH 3716")
        (field (name "MOUSER_PART_NUMBER") "720-SFH3716")
        (field (name "RS_PART_NUMBER") "1115952P")
      )
      (libsource (lib "eagle-import") (part "SFH_3716"))
    )
    (comp (ref "SFH16")
      (value "SFH_3716")
      (footprint "eagle-import:LEDC2012X89N")
      (fields
        (field (name "MANUFACTURER_PART_NUMBER") "SFH 3716")
        (field (name "MOUSER_PART_NUMBER") "720-SFH3716")
        (field (name "RS_PART_NUMBER") "1115952P")
      )
      (libsource (lib "eagle-import") (part "SFH_3716"))
    )
    (comp (ref "SFH17")
      (value "SFH_3716")
      (footprint "eagle-import:LEDC2012X89N")
      (fields
        (field (name "MANUFACTURER_PART_NUMBER") "SFH 3716")
        (field (name "MOUSER_PART_NUMBER") "720-SFH3716")
        (field (name "RS_PART_NUMBER") "1115952P")
      )
      (libsource (lib "eagle-import") (part "SFH_3716"))
    )
    (comp (ref "SFH18")
      (value "SFH_3716")
      (footprint "eagle-import:LEDC2012X89N")
      (fields
        (field (name "MANUFACTURER_PART_NUMBER") "SFH 3716")
        (field (name "MOUSER_PART_NUMBER") "720-SFH3716")
        (field (name "RS_PART_NUMBER") "1115952P")
      )
      (libsource (lib "eagle-import") (part "SFH_3716"))
    )
    (comp (ref "SFH19")
      (value "SFH_3716")
      (footprint "eagle-import:LEDC2012X89N")
      (fields
        (field (name "MANUFACTURER_PART_NUMBER") "SFH 3716")
        (field (name "MOUSER_PART_NUMBER") "720-SFH3716")
        (field (name "RS_PART_NUMBER") "1115952P")
      )
      (libsource (lib "eagle-import") (part "SFH_3716"))
    )
    (comp (ref "SFH21")
      (value "SFH_3716")
      (footprint "eagle-import:LEDC2012X89N")
      (fields
        (field (name "MANUFACTURER_PART_NUMBER") "SFH 3716")
        (field (name "MOUSER_PART_NUMBER") "720-SFH3716")
        (field (name "RS_PART_NUMBER") "1115952P")
      )
      (libsource (lib "eagle-import") (part "SFH_3716"))
    )
    (comp (ref "SFH22")
      (value "SFH_3716")
      (footprint "eagle-import:LEDC2012X89N")
      (fields
        (field (name "MANUFACTURER_PART_NUMBER") "SFH 3716")
        (field (name "MOUSER_PART_NUMBER") "720-SFH3716")
        (field (name "RS_PART_NUMBER") "1115952P")
      )
      (libsource (lib "eagle-import") (part "SFH_3716"))
    )
    (comp (ref "SFH23")
      (value "SFH_3716")
      (footprint "eagle-import:LEDC2012X89N")
      (fields
        (field (name "MANUFACTURER_PART_NUMBER") "SFH 3716")
        (field (name "MOUSER_PART_NUMBER") "720-SFH3716")
        (field (name "RS_PART_NUMBER") "1115952P")
      )
      (libsource (lib "eagle-import") (part "SFH_3716"))
    )
    (comp (ref "SFH24")
      (value "SFH_3716")
      (footprint "eagle-import:LEDC2012X89N")
      (fields
        (field (name "MANUFACTURER_PART_NUMBER") "SFH 3716")
        (field (name "MOUSER_PART_NUMBER") "720-SFH3716")
        (field (name "RS_PART_NUMBER") "1115952P")
      )
      (libsource (lib "eagle-import") (part "SFH_3716"))
    )
    (comp (ref "SFH25")
      (value "SFH_3716")
      (footprint "eagle-import:LEDC2012X89N")
      (fields
        (field (name "MANUFACTURER_PART_NUMBER") "SFH 3716")
        (field (name "MOUSER_PART_NUMBER") "720-SFH3716")
        (field (name "RS_PART_NUMBER") "1115952P")
      )
      (libsource (lib "eagle-import") (part "SFH_3716"))
    )
    (comp (ref "SFH26")
      (value "SFH_3716")
      (footprint "eagle-import:LEDC2012X89N")
      (fields
        (field (name "MANUFACTURER_PART_NUMBER") "SFH 3716")
        (field (name "MOUSER_PART_NUMBER") "720-SFH3716")
        (field (name "RS_PART_NUMBER") "1115952P")
      )
      (libsource (lib "eagle-import") (part "SFH_3716"))
    )
    (comp (ref "SFH27")
      (value "SFH_3716")
      (footprint "eagle-import:LEDC2012X89N")
      (fields
        (field (name "MANUFACTURER_PART_NUMBER") "SFH 3716")
        (field (name "MOUSER_PART_NUMBER") "720-SFH3716")
        (field (name "RS_PART_NUMBER") "1115952P")
      )
      (libsource (lib "eagle-import") (part "SFH_3716"))
    )
    (comp (ref "SFH28")
      (value "SFH_3716")
      (footprint "eagle-import:LEDC2012X89N")
      (fields
        (field (name "MANUFACTURER_PART_NUMBER") "SFH 3716")
        (field (name "MOUSER_PART_NUMBER") "720-SFH3716")
        (field (name "RS_PART_NUMBER") "1115952P")
      )
      (libsource (lib "eagle-import") (part "SFH_3716"))
    )
    (comp (ref "SFH29")
      (value "SFH_3716")
      (footprint "eagle-import:LEDC2012X89N")
      (fields
        (field (name "MANUFACTURER_PART_NUMBER") "SFH 3716")
        (field (name "MOUSER_PART_NUMBER") "720-SFH3716")
        (field (name "RS_PART_NUMBER") "1115952P")
      )
      (libsource (lib "eagle-import") (part "SFH_3716"))
    )
    (comp (ref "SFH31")
      (value "SFH_3716")
      (footprint "eagle-import:LEDC2012X89N")
      (fields
        (field (name "MANUFACTURER_PART_NUMBER") "SFH 3716")
        (field (name "MOUSER_PART_NUMBER") "720-SFH3716")
        (field (name "RS_PART_NUMBER") "1115952P")
      )
      (libsource (lib "eagle-import") (part "SFH_3716"))
    )
    (comp (ref "SFH32")
      (value "SFH_3716")
      (footprint "eagle-import:LEDC2012X89N")
      (fields
        (field (name "MANUFACTURER_PART_NUMBER") "SFH 3716")
        (field (name "MOUSER_PART_NUMBER") "720-SFH3716")
        (field (name "RS_PART_NUMBER") "1115952P")
      )
      (libsource (lib "eagle-import") (part "SFH_3716"))
    )
    (comp (ref "SFH33")
      (value "SFH_3716")
      (footprint "eagle-import:LEDC2012X89N")
      (fields
        (field (name "MANUFACTURER_PART_NUMBER") "SFH 3716")
        (field (name "MOUSER_PART_NUMBER") "720-SFH3716")
        (field (name "RS_PART_NUMBER") "1115952P")
      )
      (libsource (lib "eagle-import") (part "SFH_3716"))
    )
    (comp (ref "SFH34")
      (value "SFH_3716")
      (footprint "eagle-import:LEDC2012X89N")
      (fields
        (field (name "MANUFACTURER_PART_NUMBER") "SFH 3716")
        (field (name "MOUSER_PART_NUMBER") "720-SFH3716")
        (field (name "RS_PART_NUMBER") "1115952P")
      )
      (libsource (lib "eagle-import") (part "SFH_3716"))
    )
    (comp (ref "SFH35")
      (value "SFH_3716")
      (footprint "eagle-import:LEDC2012X89N")
      (fields
        (field (name "MANUFACTURER_PART_NUMBER") "SFH 3716")
        (field (name "MOUSER_PART_NUMBER") "720-SFH3716")
        (field (name "RS_PART_NUMBER") "1115952P")
      )
      (libsource (lib "eagle-import") (part "SFH_3716"))
    )
    (comp (ref "SFH36")
      (value "SFH_3716")
      (footprint "eagle-import:LEDC2012X89N")
      (fields
        (field (name "MANUFACTURER_PART_NUMBER") "SFH 3716")
        (field (name "MOUSER_PART_NUMBER") "720-SFH3716")
        (field (name "RS_PART_NUMBER") "1115952P")
      )
      (libsource (lib "eagle-import") (part "SFH_3716"))
    )
    (comp (ref "SFH41")
      (value "SFH_3716")
      (footprint "eagle-import:LEDC2012X89N")
      (fields
        (field (name "MANUFACTURER_PART_NUMBER") "SFH 3716")
        (field (name "MOUSER_PART_NUMBER") "720-SFH3716")
        (field (name "RS_PART_NUMBER") "1115952P")
      )
      (libsource (lib "eagle-import") (part "SFH_3716"))
    )
    (comp (ref "SFH42")
      (value "SFH_3716")
      (footprint "eagle-import:LEDC2012X89N")
      (fields
        (field (name "MANUFACTURER_PART_NUMBER") "SFH 3716")
        (field (name "MOUSER_PART_NUMBER") "720-SFH3716")
        (field (name "RS_PART_NUMBER") "1115952P")
      )
      (libsource (lib "eagle-import") (part "SFH_3716"))
    )
    (comp (ref "SFH43")
      (value "SFH_3716")
      (footprint "eagle-import:LEDC2012X89N")
      (fields
        (field (name "MANUFACTURER_PART_NUMBER") "SFH 3716")
        (field (name "MOUSER_PART_NUMBER") "720-SFH3716")
        (field (name "RS_PART_NUMBER") "1115952P")
      )
      (libsource (lib "eagle-import") (part "SFH_3716"))
    )
    (comp (ref "SFH44")
      (value "SFH_3716")
      (footprint "eagle-import:LEDC2012X89N")
      (fields
        (field (name "MANUFACTURER_PART_NUMBER") "SFH 3716")
        (field (name "MOUSER_PART_NUMBER") "720-SFH3716")
        (field (name "RS_PART_NUMBER") "1115952P")
      )
      (libsource (lib "eagle-import") (part "SFH_3716"))
    )
    (comp (ref "SFH45")
      (value "SFH_3716")
      (footprint "eagle-import:LEDC2012X89N")
      (fields
        (field (name "MANUFACTURER_PART_NUMBER") "SFH 3716")
        (field (name "MOUSER_PART_NUMBER") "720-SFH3716")
        (field (name "RS_PART_NUMBER") "1115952P")
      )
      (libsource (lib "eagle-import") (part "SFH_3716"))
    )
    (comp (ref "SFH46")
      (value "SFH_3716")
      (footprint "eagle-import:LEDC2012X89N")
      (fields
        (field (name "MANUFACTURER_PART_NUMBER") "SFH 3716")
        (field (name "MOUSER_PART_NUMBER") "720-SFH3716")
        (field (name "RS_PART_NUMBER") "1115952P")
      )
      (libsource (lib "eagle-import") (part "SFH_3716"))
    )
    (comp (ref "SFH47")
      (value "SFH_3716")
      (footprint "eagle-import:LEDC2012X89N")
      (fields
        (field (name "MANUFACTURER_PART_NUMBER") "SFH 3716")
        (field (name "MOUSER_PART_NUMBER") "720-SFH3716")
        (field (name "RS_PART_NUMBER") "1115952P")
      )
      (libsource (lib "eagle-import") (part "SFH_3716"))
    )
    (comp (ref "SFH48")
      (value "SFH_3716")
      (footprint "eagle-import:LEDC2012X89N")
      (fields
        (field (name "MANUFACTURER_PART_NUMBER") "SFH 3716")
        (field (name "MOUSER_PART_NUMBER") "720-SFH3716")
        (field (name "RS_PART_NUMBER") "1115952P")
      )
      (libsource (lib "eagle-import") (part "SFH_3716"))
    )
    (comp (ref "SFH49")
      (value "SFH_3716")
      (footprint "eagle-import:LEDC2012X89N")
      (fields
        (field (name "MANUFACTURER_PART_NUMBER") "SFH 3716")
        (field (name "MOUSER_PART_NUMBER") "720-SFH3716")
        (field (name "RS_PART_NUMBER") "1115952P")
      )
      (libsource (lib "eagle-import") (part "SFH_3716"))
    )
    (comp (ref "SFH51")
      (value "SFH_3716")
      (footprint "eagle-import:LEDC2012X89N")
      (fields
        (field (name "MANUFACTURER_PART_NUMBER") "SFH 3716")
        (field (name "MOUSER_PART_NUMBER") "720-SFH3716")
        (field (name "RS_PART_NUMBER") "1115952P")
      )
      (libsource (lib "eagle-import") (part "SFH_3716"))
    )
    (comp (ref "SFH52")
      (value "SFH_3716")
      (footprint "eagle-import:LEDC2012X89N")
      (fields
        (field (name "MANUFACTURER_PART_NUMBER") "SFH 3716")
        (field (name "MOUSER_PART_NUMBER") "720-SFH3716")
        (field (name "RS_PART_NUMBER") "1115952P")
      )
      (libsource (lib "eagle-import") (part "SFH_3716"))
    )
    (comp (ref "SFH53")
      (value "SFH_3716")
      (footprint "eagle-import:LEDC2012X89N")
      (fields
        (field (name "MANUFACTURER_PART_NUMBER") "SFH 3716")
        (field (name "MOUSER_PART_NUMBER") "720-SFH3716")
        (field (name "RS_PART_NUMBER") "1115952P")
      )
      (libsource (lib "eagle-import") (part "SFH_3716"))
    )
    (comp (ref "SFH54")
      (value "SFH_3716")
      (footprint "eagle-import:LEDC2012X89N")
      (fields
        (field (name "MANUFACTURER_PART_NUMBER") "SFH 3716")
        (field (name "MOUSER_PART_NUMBER") "720-SFH3716")
        (field (name "RS_PART_NUMBER") "1115952P")
      )
      (libsource (lib "eagle-import") (part "SFH_3716"))
    )
    (comp (ref "SFH55")
      (value "SFH_3716")
      (footprint "eagle-import:LEDC2012X89N")
      (fields
        (field (name "MANUFACTURER_PART_NUMBER") "SFH 3716")
        (field (name "MOUSER_PART_NUMBER") "720-SFH3716")
        (field (name "RS_PART_NUMBER") "1115952P")
      )
      (libsource (lib "eagle-import") (part "SFH_3716"))
    )
    (comp (ref "SFH56")
      (value "SFH_3716")
      (footprint "eagle-import:LEDC2012X89N")
      (fields
        (field (name "MANUFACTURER_PART_NUMBER") "SFH 3716")
        (field (name "MOUSER_PART_NUMBER") "720-SFH3716")
        (field (name "RS_PART_NUMBER") "1115952P")
      )
      (libsource (lib "eagle-import") (part "SFH_3716"))
    )
    (comp (ref "SFH57")
      (value "SFH_3716")
      (footprint "eagle-import:LEDC2012X89N")
      (fields
        (field (name "MANUFACTURER_PART_NUMBER") "SFH 3716")
        (field (name "MOUSER_PART_NUMBER") "720-SFH3716")
        (field (name "RS_PART_NUMBER") "1115952P")
      )
      (libsource (lib "eagle-import") (part "SFH_3716"))
    )
    (comp (ref "SFH59")
      (value "SFH_3716")
      (footprint "eagle-import:LEDC2012X89N")
      (fields
        (field (name "MANUFACTURER_PART_NUMBER") "SFH 3716")
        (field (name "MOUSER_PART_NUMBER") "720-SFH3716")
        (field (name "RS_PART_NUMBER") "1115952P")
      )
      (libsource (lib "eagle-import") (part "SFH_3716"))
    )
    (comp (ref "SFH110")
      (value "SFH_3716")
      (footprint "eagle-import:LEDC2012X89N")
      (fields
        (field (name "MANUFACTURER_PART_NUMBER") "SFH 3716")
        (field (name "MOUSER_PART_NUMBER") "720-SFH3716")
        (field (name "RS_PART_NUMBER") "1115952P")
      )
      (libsource (lib "eagle-import") (part "SFH_3716"))
    )
    (comp (ref "SFH111")
      (value "SFH_3716")
      (footprint "eagle-import:LEDC2012X89N")
      (fields
        (field (name "MANUFACTURER_PART_NUMBER") "SFH 3716")
        (field (name "MOUSER_PART_NUMBER") "720-SFH3716")
        (field (name "RS_PART_NUMBER") "1115952P")
      )
      (libsource (lib "eagle-import") (part "SFH_3716"))
    )
    (comp (ref "SFH112")
      (value "SFH_3716")
      (footprint "eagle-import:LEDC2012X89N")
      (fields
        (field (name "MANUFACTURER_PART_NUMBER") "SFH 3716")
        (field (name "MOUSER_PART_NUMBER") "720-SFH3716")
        (field (name "RS_PART_NUMBER") "1115952P")
      )
      (libsource (lib "eagle-import") (part "SFH_3716"))
    )
    (comp (ref "SFH113")
      (value "SFH_3716")
      (footprint "eagle-import:LEDC2012X89N")
      (fields
        (field (name "MANUFACTURER_PART_NUMBER") "SFH 3716")
        (field (name "MOUSER_PART_NUMBER") "720-SFH3716")
        (field (name "RS_PART_NUMBER") "1115952P")
      )
      (libsource (lib "eagle-import") (part "SFH_3716"))
    )
    (comp (ref "SFH114")
      (value "SFH_3716")
      (footprint "eagle-import:LEDC2012X89N")
      (fields
        (field (name "MANUFACTURER_PART_NUMBER") "SFH 3716")
        (field (name "MOUSER_PART_NUMBER") "720-SFH3716")
        (field (name "RS_PART_NUMBER") "1115952P")
      )
      (libsource (lib "eagle-import") (part "SFH_3716"))
    )
    (comp (ref "SFH115")
      (value "SFH_3716")
      (footprint "eagle-import:LEDC2012X89N")
      (fields
        (field (name "MANUFACTURER_PART_NUMBER") "SFH 3716")
        (field (name "MOUSER_PART_NUMBER") "720-SFH3716")
        (field (name "RS_PART_NUMBER") "1115952P")
      )
      (libsource (lib "eagle-import") (part "SFH_3716"))
    )
    (comp (ref "SFH116")
      (value "SFH_3716")
      (footprint "eagle-import:LEDC2012X89N")
      (fields
        (field (name "MANUFACTURER_PART_NUMBER") "SFH 3716")
        (field (name "MOUSER_PART_NUMBER") "720-SFH3716")
        (field (name "RS_PART_NUMBER") "1115952P")
      )
      (libsource (lib "eagle-import") (part "SFH_3716"))
    )
    (comp (ref "SFH117")
      (value "SFH_3716")
      (footprint "eagle-import:LEDC2012X89N")
      (fields
        (field (name "MANUFACTURER_PART_NUMBER") "SFH 3716")
        (field (name "MOUSER_PART_NUMBER") "720-SFH3716")
        (field (name "RS_PART_NUMBER") "1115952P")
      )
      (libsource (lib "eagle-import") (part "SFH_3716"))
    )
    (comp (ref "SFH118")
      (value "SFH_3716")
      (footprint "eagle-import:LEDC2012X89N")
      (fields
        (field (name "MANUFACTURER_PART_NUMBER") "SFH 3716")
        (field (name "MOUSER_PART_NUMBER") "720-SFH3716")
        (field (name "RS_PART_NUMBER") "1115952P")
      )
      (libsource (lib "eagle-import") (part "SFH_3716"))
    )
    (comp (ref "SFH119")
      (value "SFH_3716")
      (footprint "eagle-import:LEDC2012X89N")
      (fields
        (field (name "MANUFACTURER_PART_NUMBER") "SFH 3716")
        (field (name "MOUSER_PART_NUMBER") "720-SFH3716")
        (field (name "RS_PART_NUMBER") "1115952P")
      )
      (libsource (lib "eagle-import") (part "SFH_3716"))
    )
    (comp (ref "SFH120")
      (value "SFH_3716")
      (footprint "eagle-import:LEDC2012X89N")
      (fields
        (field (name "MANUFACTURER_PART_NUMBER") "SFH 3716")
        (field (name "MOUSER_PART_NUMBER") "720-SFH3716")
        (field (name "RS_PART_NUMBER") "1115952P")
      )
      (libsource (lib "eagle-import") (part "SFH_3716"))
    )
    (comp (ref "SFH121")
      (value "SFH_3716")
      (footprint "eagle-import:LEDC2012X89N")
      (fields
        (field (name "MANUFACTURER_PART_NUMBER") "SFH 3716")
        (field (name "MOUSER_PART_NUMBER") "720-SFH3716")
        (field (name "RS_PART_NUMBER") "1115952P")
      )
      (libsource (lib "eagle-import") (part "SFH_3716"))
    )
    (comp (ref "SFH122")
      (value "SFH_3716")
      (footprint "eagle-import:LEDC2012X89N")
      (fields
        (field (name "MANUFACTURER_PART_NUMBER") "SFH 3716")
        (field (name "MOUSER_PART_NUMBER") "720-SFH3716")
        (field (name "RS_PART_NUMBER") "1115952P")
      )
      (libsource (lib "eagle-import") (part "SFH_3716"))
    )
    (comp (ref "SFH123")
      (value "SFH_3716")
      (footprint "eagle-import:LEDC2012X89N")
      (fields
        (field (name "MANUFACTURER_PART_NUMBER") "SFH 3716")
        (field (name "MOUSER_PART_NUMBER") "720-SFH3716")
        (field (name "RS_PART_NUMBER") "1115952P")
      )
      (libsource (lib "eagle-import") (part "SFH_3716"))
    )
    (comp (ref "SFH124")
      (value "SFH_3716")
      (footprint "eagle-import:LEDC2012X89N")
      (fields
        (field (name "MANUFACTURER_PART_NUMBER") "SFH 3716")
        (field (name "MOUSER_PART_NUMBER") "720-SFH3716")
        (field (name "RS_PART_NUMBER") "1115952P")
      )
      (libsource (lib "eagle-import") (part "SFH_3716"))
    )
    (comp (ref "SFH210")
      (value "SFH_3716")
      (footprint "eagle-import:LEDC2012X89N")
      (fields
        (field (name "MANUFACTURER_PART_NUMBER") "SFH 3716")
        (field (name "MOUSER_PART_NUMBER") "720-SFH3716")
        (field (name "RS_PART_NUMBER") "1115952P")
      )
      (libsource (lib "eagle-import") (part "SFH_3716"))
    )
    (comp (ref "SFH211")
      (value "SFH_3716")
      (footprint "eagle-import:LEDC2012X89N")
      (fields
        (field (name "MANUFACTURER_PART_NUMBER") "SFH 3716")
        (field (name "MOUSER_PART_NUMBER") "720-SFH3716")
        (field (name "RS_PART_NUMBER") "1115952P")
      )
      (libsource (lib "eagle-import") (part "SFH_3716"))
    )
    (comp (ref "SFH212")
      (value "SFH_3716")
      (footprint "eagle-import:LEDC2012X89N")
      (fields
        (field (name "MANUFACTURER_PART_NUMBER") "SFH 3716")
        (field (name "MOUSER_PART_NUMBER") "720-SFH3716")
        (field (name "RS_PART_NUMBER") "1115952P")
      )
      (libsource (lib "eagle-import") (part "SFH_3716"))
    )
    (comp (ref "SFH213")
      (value "SFH_3716")
      (footprint "eagle-import:LEDC2012X89N")
      (fields
        (field (name "MANUFACTURER_PART_NUMBER") "SFH 3716")
        (field (name "MOUSER_PART_NUMBER") "720-SFH3716")
        (field (name "RS_PART_NUMBER") "1115952P")
      )
      (libsource (lib "eagle-import") (part "SFH_3716"))
    )
    (comp (ref "SFH214")
      (value "SFH_3716")
      (footprint "eagle-import:LEDC2012X89N")
      (fields
        (field (name "MANUFACTURER_PART_NUMBER") "SFH 3716")
        (field (name "MOUSER_PART_NUMBER") "720-SFH3716")
        (field (name "RS_PART_NUMBER") "1115952P")
      )
      (libsource (lib "eagle-import") (part "SFH_3716"))
    )
    (comp (ref "SFH215")
      (value "SFH_3716")
      (footprint "eagle-import:LEDC2012X89N")
      (fields
        (field (name "MANUFACTURER_PART_NUMBER") "SFH 3716")
        (field (name "MOUSER_PART_NUMBER") "720-SFH3716")
        (field (name "RS_PART_NUMBER") "1115952P")
      )
      (libsource (lib "eagle-import") (part "SFH_3716"))
    )
    (comp (ref "SFH216")
      (value "SFH_3716")
      (footprint "eagle-import:LEDC2012X89N")
      (fields
        (field (name "MANUFACTURER_PART_NUMBER") "SFH 3716")
        (field (name "MOUSER_PART_NUMBER") "720-SFH3716")
        (field (name "RS_PART_NUMBER") "1115952P")
      )
      (libsource (lib "eagle-import") (part "SFH_3716"))
    )
    (comp (ref "SFH217")
      (value "SFH_3716")
      (footprint "eagle-import:LEDC2012X89N")
      (fields
        (field (name "MANUFACTURER_PART_NUMBER") "SFH 3716")
        (field (name "MOUSER_PART_NUMBER") "720-SFH3716")
        (field (name "RS_PART_NUMBER") "1115952P")
      )
      (libsource (lib "eagle-import") (part "SFH_3716"))
    )
    (comp (ref "SFH218")
      (value "SFH_3716")
      (footprint "eagle-import:LEDC2012X89N")
      (fields
        (field (name "MANUFACTURER_PART_NUMBER") "SFH 3716")
        (field (name "MOUSER_PART_NUMBER") "720-SFH3716")
        (field (name "RS_PART_NUMBER") "1115952P")
      )
      (libsource (lib "eagle-import") (part "SFH_3716"))
    )
    (comp (ref "SFH219")
      (value "SFH_3716")
      (footprint "eagle-import:LEDC2012X89N")
      (fields
        (field (name "MANUFACTURER_PART_NUMBER") "SFH 3716")
        (field (name "MOUSER_PART_NUMBER") "720-SFH3716")
        (field (name "RS_PART_NUMBER") "1115952P")
      )
      (libsource (lib "eagle-import") (part "SFH_3716"))
    )
    (comp (ref "SFH220")
      (value "SFH_3716")
      (footprint "eagle-import:LEDC2012X89N")
      (fields
        (field (name "MANUFACTURER_PART_NUMBER") "SFH 3716")
        (field (name "MOUSER_PART_NUMBER") "720-SFH3716")
        (field (name "RS_PART_NUMBER") "1115952P")
      )
      (libsource (lib "eagle-import") (part "SFH_3716"))
    )
    (comp (ref "SFH221")
      (value "SFH_3716")
      (footprint "eagle-import:LEDC2012X89N")
      (fields
        (field (name "MANUFACTURER_PART_NUMBER") "SFH 3716")
        (field (name "MOUSER_PART_NUMBER") "720-SFH3716")
        (field (name "RS_PART_NUMBER") "1115952P")
      )
      (libsource (lib "eagle-import") (part "SFH_3716"))
    )
    (comp (ref "SFH222")
      (value "SFH_3716")
      (footprint "eagle-import:LEDC2012X89N")
      (fields
        (field (name "MANUFACTURER_PART_NUMBER") "SFH 3716")
        (field (name "MOUSER_PART_NUMBER") "720-SFH3716")
        (field (name "RS_PART_NUMBER") "1115952P")
      )
      (libsource (lib "eagle-import") (part "SFH_3716"))
    )
    (comp (ref "SFH223")
      (value "SFH_3716")
      (footprint "eagle-import:LEDC2012X89N")
      (fields
        (field (name "MANUFACTURER_PART_NUMBER") "SFH 3716")
        (field (name "MOUSER_PART_NUMBER") "720-SFH3716")
        (field (name "RS_PART_NUMBER") "1115952P")
      )
      (libsource (lib "eagle-import") (part "SFH_3716"))
    )
    (comp (ref "SFH224")
      (value "SFH_3716")
      (footprint "eagle-import:LEDC2012X89N")
      (fields
        (field (name "MANUFACTURER_PART_NUMBER") "SFH 3716")
        (field (name "MOUSER_PART_NUMBER") "720-SFH3716")
        (field (name "RS_PART_NUMBER") "1115952P")
      )
      (libsource (lib "eagle-import") (part "SFH_3716"))
    )
    (comp (ref "SFH225")
      (value "SFH_3716")
      (footprint "eagle-import:LEDC2012X89N")
      (fields
        (field (name "MANUFACTURER_PART_NUMBER") "SFH 3716")
        (field (name "MOUSER_PART_NUMBER") "720-SFH3716")
        (field (name "RS_PART_NUMBER") "1115952P")
      )
      (libsource (lib "eagle-import") (part "SFH_3716"))
    )
    (comp (ref "SFH226")
      (value "SFH_3716")
      (footprint "eagle-import:LEDC2012X89N")
      (fields
        (field (name "MANUFACTURER_PART_NUMBER") "SFH 3716")
        (field (name "MOUSER_PART_NUMBER") "720-SFH3716")
        (field (name "RS_PART_NUMBER") "1115952P")
      )
      (libsource (lib "eagle-import") (part "SFH_3716"))
    )
    (comp (ref "SFH227")
      (value "SFH_3716")
      (footprint "eagle-import:LEDC2012X89N")
      (fields
        (field (name "MANUFACTURER_PART_NUMBER") "SFH 3716")
        (field (name "MOUSER_PART_NUMBER") "720-SFH3716")
        (field (name "RS_PART_NUMBER") "1115952P")
      )
      (libsource (lib "eagle-import") (part "SFH_3716"))
    )
    (comp (ref "SFH228")
      (value "SFH_3716")
      (footprint "eagle-import:LEDC2012X89N")
      (fields
        (field (name "MANUFACTURER_PART_NUMBER") "SFH 3716")
        (field (name "MOUSER_PART_NUMBER") "720-SFH3716")
        (field (name "RS_PART_NUMBER") "1115952P")
      )
      (libsource (lib "eagle-import") (part "SFH_3716"))
    )
    (comp (ref "SFH229")
      (value "SFH_3716")
      (footprint "eagle-import:LEDC2012X89N")
      (fields
        (field (name "MANUFACTURER_PART_NUMBER") "SFH 3716")
        (field (name "MOUSER_PART_NUMBER") "720-SFH3716")
        (field (name "RS_PART_NUMBER") "1115952P")
      )
      (libsource (lib "eagle-import") (part "SFH_3716"))
    )
    (comp (ref "SFH230")
      (value "SFH_3716")
      (footprint "eagle-import:LEDC2012X89N")
      (fields
        (field (name "MANUFACTURER_PART_NUMBER") "SFH 3716")
        (field (name "MOUSER_PART_NUMBER") "720-SFH3716")
        (field (name "RS_PART_NUMBER") "1115952P")
      )
      (libsource (lib "eagle-import") (part "SFH_3716"))
    )
    (comp (ref "SFH231")
      (value "SFH_3716")
      (footprint "eagle-import:LEDC2012X89N")
      (fields
        (field (name "MANUFACTURER_PART_NUMBER") "SFH 3716")
        (field (name "MOUSER_PART_NUMBER") "720-SFH3716")
        (field (name "RS_PART_NUMBER") "1115952P")
      )
      (libsource (lib "eagle-import") (part "SFH_3716"))
    )
    (comp (ref "SFH232")
      (value "SFH_3716")
      (footprint "eagle-import:LEDC2012X89N")
      (fields
        (field (name "MANUFACTURER_PART_NUMBER") "SFH 3716")
        (field (name "MOUSER_PART_NUMBER") "720-SFH3716")
        (field (name "RS_PART_NUMBER") "1115952P")
      )
      (libsource (lib "eagle-import") (part "SFH_3716"))
    )
    (comp (ref "SFH410")
      (value "SFH_3716")
      (footprint "eagle-import:LEDC2012X89N")
      (fields
        (field (name "MANUFACTURER_PART_NUMBER") "SFH 3716")
        (field (name "MOUSER_PART_NUMBER") "720-SFH3716")
        (field (name "RS_PART_NUMBER") "1115952P")
      )
      (libsource (lib "eagle-import") (part "SFH_3716"))
    )
    (comp (ref "SFH411")
      (value "SFH_3716")
      (footprint "eagle-import:LEDC2012X89N")
      (fields
        (field (name "MANUFACTURER_PART_NUMBER") "SFH 3716")
        (field (name "MOUSER_PART_NUMBER") "720-SFH3716")
        (field (name "RS_PART_NUMBER") "1115952P")
      )
      (libsource (lib "eagle-import") (part "SFH_3716"))
    )
    (comp (ref "SFH412")
      (value "SFH_3716")
      (footprint "eagle-import:LEDC2012X89N")
      (fields
        (field (name "MANUFACTURER_PART_NUMBER") "SFH 3716")
        (field (name "MOUSER_PART_NUMBER") "720-SFH3716")
        (field (name "RS_PART_NUMBER") "1115952P")
      )
      (libsource (lib "eagle-import") (part "SFH_3716"))
    )
    (comp (ref "SFH510")
      (value "SFH_3716")
      (footprint "eagle-import:LEDC2012X89N")
      (fields
        (field (name "MANUFACTURER_PART_NUMBER") "SFH 3716")
        (field (name "MOUSER_PART_NUMBER") "720-SFH3716")
        (field (name "RS_PART_NUMBER") "1115952P")
      )
      (libsource (lib "eagle-import") (part "SFH_3716"))
    )
    (comp (ref "SFH511")
      (value "SFH_3716")
      (footprint "eagle-import:LEDC2012X89N")
      (fields
        (field (name "MANUFACTURER_PART_NUMBER") "SFH 3716")
        (field (name "MOUSER_PART_NUMBER") "720-SFH3716")
        (field (name "RS_PART_NUMBER") "1115952P")
      )
      (libsource (lib "eagle-import") (part "SFH_3716"))
    )
    (comp (ref "LED5")
      (value "SFH_4656-Z")
      (footprint "eagle-import:SFH4656Z")
      (fields
        (field (name "MANUFACTURER_PART_NUMBER") "SFH 4656-Z")
        (field (name "MOUSER_PART_NUMBER") "720-SFH4656-Z")
      )
      (libsource (lib "eagle-import") (part "SFH_4656-Z"))
    )
    (comp (ref "LED06")
      (value "SFH_4656-Z")
      (footprint "eagle-import:SFH4656Z")
      (fields
        (field (name "MANUFACTURER_PART_NUMBER") "SFH 4656-Z")
        (field (name "MOUSER_PART_NUMBER") "720-SFH4656-Z")
      )
      (libsource (lib "eagle-import") (part "SFH_4656-Z"))
    )
    (comp (ref "LED09")
      (value "SFH_4656-Z")
      (footprint "eagle-import:SFH4656Z")
      (fields
        (field (name "MANUFACTURER_PART_NUMBER") "SFH 4656-Z")
        (field (name "MOUSER_PART_NUMBER") "720-SFH4656-Z")
      )
      (libsource (lib "eagle-import") (part "SFH_4656-Z"))
    )
    (comp (ref "LED10")
      (value "SFH_4656-Z")
      (footprint "eagle-import:SFH4656Z")
      (fields
        (field (name "MANUFACTURER_PART_NUMBER") "SFH 4656-Z")
        (field (name "MOUSER_PART_NUMBER") "720-SFH4656-Z")
      )
      (libsource (lib "eagle-import") (part "SFH_4656-Z"))
    )
    (comp (ref "LED41")
      (value "POWER_LED-GREEN-CHIPLED_0805")
      (footprint "eagle-import:POWER_DISTRIBUTION_CHIPLED_0805")
      (fields (field (name "MF") "Würth Elektronik") (field (name "MPN") "150080GS75000"))
      (libsource (lib "eagle-import") (part "POWER_LEDCHIPLED_0805-GREEN-"))
    )
    (comp (ref "Q1")
      (value "AP2012P3C-P22")
      (footprint "eagle-import:AP2012P3CP22")
      (fields (field (name "MOUSER_PART_NUMBER") "604-AP2012P3C-P22"))
      (libsource (lib "eagle-import") (part "AP2012P3C-P22"))
    )
    (comp (ref "Q2")
      (value "AP2012P3C-P22")
      (footprint "eagle-import:AP2012P3CP22")
      (fields (field (name "MOUSER_PART_NUMBER") "604-AP2012P3C-P22"))
      (libsource (lib "eagle-import") (part "AP2012P3C-P22"))
    )
    (comp (ref "Q5")
      (value "AP2012P3C-P22")
      (footprint "eagle-import:AP2012P3CP22")
      (fields (field (name "MOUSER_PART_NUMBER") "604-AP2012P3C-P22"))
      (libsource (lib "eagle-import") (part "AP2012P3C-P22"))
    )
    (comp (ref "Q6")
      (value "AP2012P3C-P22")
      (footprint "eagle-import:AP2012P3CP22")
      (fields (field (name "MOUSER_PART_NUMBER") "604-AP2012P3C-P22"))
      (libsource (lib "eagle-import") (part "AP2012P3C-P22"))
    )
    (comp (ref "R08")
      (value "10k")
      (footprint "eagle-import:R0603")
      (libsource (lib "eagle-import") (part "R-EU_R0603"))
    )
    (comp (ref "R09")
      (value "1k")
      (footprint "eagle-import:R0603")
      (libsource (lib "eagle-import") (part "R-EU_R0603"))
    )
    (comp (ref "R32")
      (value "10k")
      (footprint "eagle-import:R0603")
      (libsource (lib "eagle-import") (part "R-EU_R0603"))
    )
    (comp (ref "R33")
      (value "1k")
      (footprint "eagle-import:R0603")
      (libsource (lib "eagle-import") (part "R-EU_R0603"))
    )
    (comp (ref "R34")
      (value "10k")
      (footprint "eagle-import:R0603")
      (libsource (lib "eagle-import") (part "R-EU_R0603"))
    )
    (comp (ref "R35")
      (value "1k")
      (footprint "eagle-import:R0603")
      (libsource (lib "eagle-import") (part "R-EU_R0603"))
    )
    (comp (ref "R42")
      (value "10k")
      (footprint "eagle-import:R0603")
      (libsource (lib "eagle-import") (part "R-EU_R0603"))
    )
    (comp (ref "R43")
      (value "1k")
      (footprint "eagle-import:R0603")
      (libsource (lib "eagle-import") (part "R-EU_R0603"))
    )
    (comp (ref "R58")
      (value "1k")
      (footprint "eagle-import:R0603")
      (libsource (lib "eagle-import") (part "R-EU_R0603"))
    )
  )
  (nets
    (net (code "1") (name "+3V3") (class "Default")
      (node (ref "JP2") (pin "2") (pinfunction "2_2") (pintype "passive"))
      (node (ref "LED06") (pin "1") (pinfunction "A_1") (pintype "bidirectional"))
      (node (ref "LED09") (pin "1") (pinfunction "A_1") (pintype "bidirectional"))
      (node (ref "LED10") (pin "1") (pinfunction "A_1") (pintype "bidirectional"))
      (node (ref "LED5") (pin "1") (pinfunction "A_1") (pintype "bidirectional"))
      (node (ref "Q1") (pin "1") (pinfunction "C_1") (pintype "bidirectional"))
      (node (ref "Q2") (pin "1") (pinfunction "C_1") (pintype "bidirectional"))
      (node (ref "Q5") (pin "1") (pinfunction "C_1") (pintype "bidirectional"))
      (node (ref "Q6") (pin "1") (pinfunction "C_1") (pintype "bidirectional"))
      (node (ref "R01") (pin "2") (pinfunction "2_2") (pintype "passive"))
      (node (ref "R02") (pin "2") (pinfunction "2_2") (pintype "passive"))
      (node (ref "R03") (pin "2") (pinfunction "2_2") (pintype "passive"))
      (node (ref "R04") (pin "2") (pinfunction "2_2") (pintype "passive"))
      (node (ref "R05") (pin "2") (pinfunction "2_2") (pintype "passive"))
      (node (ref "R06") (pin "2") (pinfunction "2_2") (pintype "passive"))
      (node (ref "R07") (pin "2") (pinfunction "2_2") (pintype "passive"))
      (node (ref "R11") (pin "2") (pinfunction "2_2") (pintype "passive"))
      (node (ref "R110") (pin "2") (pinfunction "2_2") (pintype "passive"))
      (node (ref "R111") (pin "2") (pinfunction "2_2") (pintype "passive"))
      (node (ref "R112") (pin "2") (pinfunction "2_2") (pintype "passive"))
      (node (ref "R12") (pin "2") (pinfunction "2_2") (pintype "passive"))
      (node (ref "R13") (pin "2") (pinfunction "2_2") (pintype "passive"))
      (node (ref "R14") (pin "2") (pinfunction "2_2") (pintype "passive"))
      (node (ref "R15") (pin "2") (pinfunction "2_2") (pintype "passive"))
      (node (ref "R16") (pin "2") (pinfunction "2_2") (pintype "passive"))
      (node (ref "R17") (pin "2") (pinfunction "2_2") (pintype "passive"))
      (node (ref "R18") (pin "2") (pinfunction "2_2") (pintype "passive"))
      (node (ref "R19") (pin "2") (pinfunction "2_2") (pintype "passive"))
      (node (ref "R21") (pin "2") (pinfunction "2_2") (pintype "passive"))
      (node (ref "R210") (pin "2") (pinfunction "2_2") (pintype "passive"))
      (node (ref "R211") (pin "2") (pinfunction "2_2") (pintype "passive"))
      (node (ref "R212") (pin "2") (pinfunction "2_2") (pintype "passive"))
      (node (ref "R213") (pin "2") (pinfunction "2_2") (pintype "passive"))
      (node (ref "R214") (pin "2") (pinfunction "2_2") (pintype "passive"))
      (node (ref "R215") (pin "2") (pinfunction "2_2") (pintype "passive"))
      (node (ref "R216") (pin "2") (pinfunction "2_2") (pintype "passive"))
      (node (ref "R22") (pin "2") (pinfunction "2_2") (pintype "passive"))
      (node (ref "R23") (pin "2") (pinfunction "2_2") (pintype "passive"))
      (node (ref "R24") (pin "2") (pinfunction "2_2") (pintype "passive"))
      (node (ref "R25") (pin "2") (pinfunction "2_2") (pintype "passive"))
      (node (ref "R26") (pin "2") (pinfunction "2_2") (pintype "passive"))
      (node (ref "R27") (pin "2") (pinfunction "2_2") (pintype "passive"))
      (node (ref "R28") (pin "2") (pinfunction "2_2") (pintype "passive"))
      (node (ref "R29") (pin "2") (pinfunction "2_2") (pintype "passive"))
      (node (ref "SFH01") (pin "2") (pinfunction "A_2") (pintype "bidirectional"))
      (node (ref "SFH02") (pin "2") (pinfunction "A_2") (pintype "bidirectional"))
      (node (ref "SFH03") (pin "2") (pinfunction "A_2") (pintype "bidirectional"))
      (node (ref "SFH04") (pin "2") (pinfunction "A_2") (pintype "bidirectional"))
      (node (ref "SFH05") (pin "2") (pinfunction "A_2") (pintype "bidirectional"))
      (node (ref "SFH06") (pin "2") (pinfunction "A_2") (pintype "bidirectional"))
      (node (ref "SFH07") (pin "2") (pinfunction "A_2") (pintype "bidirectional"))
      (node (ref "SFH08") (pin "2") (pinfunction "A_2") (pintype "bidirectional"))
      (node (ref "SFH11") (pin "2") (pinfunction "A_2") (pintype "bidirectional"))
      (node (ref "SFH110") (pin "2") (pinfunction "A_2") (pintype "bidirectional"))
      (node (ref "SFH111") (pin "2") (pinfunction "A_2") (pintype "bidirectional"))
      (node (ref "SFH112") (pin "2") (pinfunction "A_2") (pintype "bidirectional"))
      (node (ref "SFH113") (pin "2") (pinfunction "A_2") (pintype "bidirectional"))
      (node (ref "SFH114") (pin "2") (pinfunction "A_2") (pintype "bidirectional"))
      (node (ref "SFH115") (pin "2") (pinfunction "A_2") (pintype "bidirectional"))
      (node (ref "SFH116") (pin "2") (pinfunction "A_2") (pintype "bidirectional"))
      (node (ref "SFH117") (pin "2") (pinfunction "A_2") (pintype "bidirectional"))
      (node (ref "SFH118") (pin "2") (pinfunction "A_2") (pintype "bidirectional"))
      (node (ref "SFH119") (pin "2") (pinfunction "A_2") (pintype "bidirectional"))
      (node (ref "SFH12") (pin "2") (pinfunction "A_2") (pintype "bidirectional"))
      (node (ref "SFH120") (pin "2") (pinfunction "A_2") (pintype "bidirectional"))
      (node (ref "SFH121") (pin "2") (pinfunction "A_2") (pintype "bidirectional"))
      (node (ref "SFH122") (pin "2") (pinfunction "A_2") (pintype "bidirectional"))
      (node (ref "SFH123") (pin "2") (pinfunction "A_2") (pintype "bidirectional"))
      (node (ref "SFH124") (pin "2") (pinfunction "A_2") (pintype "bidirectional"))
      (node (ref "SFH13") (pin "2") (pinfunction "A_2") (pintype "bidirectional"))
      (node (ref "SFH14") (pin "2") (pinfunction "A_2") (pintype "bidirectional"))
      (node (ref "SFH15") (pin "2") (pinfunction "A_2") (pintype "bidirectional"))
      (node (ref "SFH16") (pin "2") (pinfunction "A_2") (pintype "bidirectional"))
      (node (ref "SFH17") (pin "2") (pinfunction "A_2") (pintype "bidirectional"))
      (node (ref "SFH18") (pin "2") (pinfunction "A_2") (pintype "bidirectional"))
      (node (ref "SFH19") (pin "2") (pinfunction "A_2") (pintype "bidirectional"))
      (node (ref "SFH21") (pin "2") (pinfunction "A_2") (pintype "bidirectional"))
      (node (ref "SFH210") (pin "2") (pinfunction "A_2") (pintype "bidirectional"))
      (node (ref "SFH211") (pin "2") (pinfunction "A_2") (pintype "bidirectional"))
      (node (ref "SFH212") (pin "2") (pinfunction "A_2") (pintype "bidirectional"))
      (node (ref "SFH213") (pin "2") (pinfunction "A_2") (pintype "bidirectional"))
      (node (ref "SFH214") (pin "2") (pinfunction "A_2") (pintype "bidirectional"))
      (node (ref "SFH215") (pin "2") (pinfunction "A_2") (pintype "bidirectional"))
      (node (ref "SFH216") (pin "2") (pinfunction "A_2") (pintype "bidirectional"))
      (node (ref "SFH217") (pin "2") (pinfunction "A_2") (pintype "bidirectional"))
      (node (ref "SFH218") (pin "2") (pinfunction "A_2") (pintype "bidirectional"))
      (node (ref "SFH219") (pin "2") (pinfunction "A_2") (pintype "bidirectional"))
      (node (ref "SFH22") (pin "2") (pinfunction "A_2") (pintype "bidirectional"))
      (node (ref "SFH220") (pin "2") (pinfunction "A_2") (pintype "bidirectional"))
      (node (ref "SFH221") (pin "2") (pinfunction "A_2") (pintype "bidirectional"))
      (node (ref "SFH222") (pin "2") (pinfunction "A_2") (pintype "bidirectional"))
      (node (ref "SFH223") (pin "2") (pinfunction "A_2") (pintype "bidirectional"))
      (node (ref "SFH224") (pin "2") (pinfunction "A_2") (pintype "bidirectional"))
      (node (ref "SFH225") (pin "2") (pinfunction "A_2") (pintype "bidirectional"))
      (node (ref "SFH226") (pin "2") (pinfunction "A_2") (pintype "bidirectional"))
      (node (ref "SFH227") (pin "2") (pinfunction "A_2") (pintype "bidirectional"))
      (node (ref "SFH228") (pin "2") (pinfunction "A_2") (pintype "bidirectional"))
      (node (ref "SFH229") (pin "2") (pinfunction "A_2") (pintype "bidirectional"))
      (node (ref "SFH23") (pin "2") (pinfunction "A_2") (pintype "bidirectional"))
      (node (ref "SFH230") (pin "2") (pinfunction "A_2") (pintype "bidirectional"))
      (node (ref "SFH231") (pin "2") (pinfunction "A_2") (pintype "bidirectional"))
      (node (ref "SFH232") (pin "2") (pinfunction "A_2") (pintype "bidirectional"))
      (node (ref "SFH24") (pin "2") (pinfunction "A_2") (pintype "bidirectional"))
      (node (ref "SFH25") (pin "2") (pinfunction "A_2") (pintype "bidirectional"))
      (node (ref "SFH26") (pin "2") (pinfunction "A_2") (pintype "bidirectional"))
      (node (ref "SFH27") (pin "2") (pinfunction "A_2") (pintype "bidirectional"))
      (node (ref "SFH28") (pin "2") (pinfunction "A_2") (pintype "bidirectional"))
      (node (ref "SFH29") (pin "2") (pinfunction "A_2") (pintype "bidirectional"))
      (node (ref "SFH31") (pin "2") (pinfunction "A_2") (pintype "bidirectional"))
      (node (ref "SFH32") (pin "2") (pinfunction "A_2") (pintype "bidirectional"))
      (node (ref "SFH33") (pin "2") (pinfunction "A_2") (pintype "bidirectional"))
      (node (ref "SFH34") (pin "2") (pinfunction "A_2") (pintype "bidirectional"))
      (node (ref "SFH35") (pin "2") (pinfunction "A_2") (pintype "bidirectional"))
      (node (ref "SFH36") (pin "2") (pinfunction "A_2") (pintype "bidirectional"))
      (node (ref "SFH41") (pin "2") (pinfunction "A_2") (pintype "bidirectional"))
      (node (ref "SFH410") (pin "2") (pinfunction "A_2") (pintype "bidirectional"))
      (node (ref "SFH411") (pin "2") (pinfunction "A_2") (pintype "bidirectional"))
      (node (ref "SFH412") (pin "2") (pinfunction "A_2") (pintype "bidirectional"))
      (node (ref "SFH42") (pin "2") (pinfunction "A_2") (pintype "bidirectional"))
      (node (ref "SFH43") (pin "2") (pinfunction "A_2") (pintype "bidirectional"))
      (node (ref "SFH44") (pin "2") (pinfunction "A_2") (pintype "bidirectional"))
      (node (ref "SFH45") (pin "2") (pinfunction "A_2") (pintype "bidirectional"))
      (node (ref "SFH46") (pin "2") (pinfunction "A_2") (pintype "bidirectional"))
      (node (ref "SFH47") (pin "2") (pinfunction "A_2") (pintype "bidirectional"))
      (node (ref "SFH48") (pin "2") (pinfunction "A_2") (pintype "bidirectional"))
      (node (ref "SFH49") (pin "2") (pinfunction "A_2") (pintype "bidirectional"))
      (node (ref "SFH51") (pin "2") (pinfunction "A_2") (pintype "bidirectional"))
      (node (ref "SFH510") (pin "2") (pinfunction "A_2") (pintype "bidirectional"))
      (node (ref "SFH511") (pin "2") (pinfunction "A_2") (pintype "bidirectional"))
      (node (ref "SFH52") (pin "2") (pinfunction "A_2") (pintype "bidirectional"))
      (node (ref "SFH53") (pin "2") (pinfunction "A_2") (pintype "bidirectional"))
      (node (ref "SFH54") (pin "2") (pinfunction "A_2") (pintype "bidirectional"))
      (node (ref "SFH55") (pin "2") (pinfunction "A_2") (pintype "bidirectional"))
      (node (ref "SFH56") (pin "2") (pinfunction "A_2") (pintype "bidirectional"))
      (node (ref "SFH57") (pin "2") (pinfunction "A_2") (pintype "bidirectional"))
      (node (ref "SFH59") (pin "2") (pinfunction "A_2") (pintype "bidirectional"))
    )
    (net (code "2") (name "+5V") (class "Default")
      (node (ref "JP2") (pin "3") (pinfunction "3_3") (pintype "passive"))
      (node (ref "LED41") (pin "A") (pinfunction "A_A") (pintype "passive"))
      (node (ref "M0") (pin "24") (pinfunction "VCC_24") (pintype "bidirectional"))
      (node (ref "M1") (pin "24") (pinfunction "VCC_24") (pintype "bidirectional"))
      (node (ref "M2") (pin "24") (pinfunction "VCC_24") (pintype "bidirectional"))
      (node (ref "M3") (pin "24") (pinfunction "VCC_24") (pintype "bidirectional"))
      (node (ref "M4") (pin "24") (pinfunction "VCC_24") (pintype "bidirectional"))
      (node (ref "M5") (pin "24") (pinfunction "VCC_24") (pintype "bidirectional"))
    )
    (net (code "3") (name "01") (class "Default")
      (node (ref "M5") (pin "16") (pinfunction "CHAN15_16") (pintype "bidirectional"))
      (node (ref "RP01") (pin "2") (pinfunction "2_2") (pintype "passive"))
      (node (ref "SFH01") (pin "1") (pinfunction "K_1") (pintype "bidirectional"))
    )
    (net (code "4") (name "02") (class "Default")
      (node (ref "M4") (pin "9") (pinfunction "CHAN0_9") (pintype "bidirectional"))
      (node (ref "RP02") (pin "2") (pinfunction "2_2") (pintype "passive"))
      (node (ref "SFH02") (pin "1") (pinfunction "K_1") (pintype "bidirectional"))
    )
    (net (code "5") (name "03") (class "Default")
      (node (ref "M3") (pin "19") (pinfunction "CHAN12_19") (pintype "bidirectional"))
      (node (ref "RP03") (pin "2") (pinfunction "2_2") (pintype "passive"))
      (node (ref "SFH03") (pin "1") (pinfunction "K_1") (pintype "bidirectional"))
    )
    (net (code "6") (name "04") (class "Default")
      (node (ref "M3") (pin "20") (pinfunction "CHAN11_20") (pintype "bidirectional"))
      (node (ref "RP04") (pin "2") (pinfunction "2_2") (pintype "passive"))
      (node (ref "SFH04") (pin "1") (pinfunction "K_1") (pintype "bidirectional"))
    )
    (net (code "7") (name "05") (class "Default")
      (node (ref "M2") (pin "9") (pinfunction "CHAN0_9") (pintype "bidirectional"))
      (node (ref "RP05") (pin "2") (pinfunction "2_2") (pintype "passive"))
      (node (ref "SFH05") (pin "1") (pinfunction "K_1") (pintype "bidirectional"))
    )
    (net (code "8") (name "06") (class "Default")
      (node (ref "M3") (pin "16") (pinfunction "CHAN15_16") (pintype "bidirectional"))
      (node (ref "RP06") (pin "2") (pinfunction "2_2") (pintype "passive"))
      (node (ref "SFH06") (pin "1") (pinfunction "K_1") (pintype "bidirectional"))
    )
    (net (code "9") (name "07") (class "Default")
      (node (ref "M2") (pin "6") (pinfunction "CHAN3_6") (pintype "bidirectional"))
      (node (ref "RP07") (pin "2") (pinfunction "2_2") (pintype "passive"))
      (node (ref "SFH07") (pin "1") (pinfunction "K_1") (pintype "bidirectional"))
    )
    (net (code "10") (name "08") (class "Default")
      (node (ref "M2") (pin "5") (pinfunction "CHAN4_5") (pintype "bidirectional"))
      (node (ref "RP08") (pin "2") (pinfunction "2_2") (pintype "passive"))
      (node (ref "SFH08") (pin "1") (pinfunction "K_1") (pintype "bidirectional"))
    )
    (net (code "11") (name "11") (class "Default")
      (node (ref "M3") (pin "5") (pinfunction "CHAN4_5") (pintype "bidirectional"))
      (node (ref "RP11") (pin "2") (pinfunction "2_2") (pintype "passive"))
      (node (ref "SFH11") (pin "1") (pinfunction "K_1") (pintype "bidirectional"))
    )
    (net (code "12") (name "12") (class "Default")
      (node (ref "M3") (pin "6") (pinfunction "CHAN3_6") (pintype "bidirectional"))
      (node (ref "RP12") (pin "2") (pinfunction "2_2") (pintype "passive"))
      (node (ref "SFH12") (pin "1") (pinfunction "K_1") (pintype "bidirectional"))
    )
    (net (code "13") (name "13") (class "Default")
      (node (ref "M3") (pin "7") (pinfunction "CHAN2_7") (pintype "bidirectional"))
      (node (ref "RP13") (pin "2") (pinfunction "2_2") (pintype "passive"))
      (node (ref "SFH13") (pin "1") (pinfunction "K_1") (pintype "bidirectional"))
    )
    (net (code "14") (name "14") (class "Default")
      (node (ref "M1") (pin "2") (pinfunction "CHAN7_2") (pintype "bidirectional"))
      (node (ref "RP14") (pin "2") (pinfunction "2_2") (pintype "passive"))
      (node (ref "SFH14") (pin "1") (pinfunction "K_1") (pintype "bidirectional"))
    )
    (net (code "15") (name "15") (class "Default")
      (node (ref "M1") (pin "16") (pinfunction "CHAN15_16") (pintype "bidirectional"))
      (node (ref "RP15") (pin "2") (pinfunction "2_2") (pintype "passive"))
      (node (ref "SFH15") (pin "1") (pinfunction "K_1") (pintype "bidirectional"))
    )
    (net (code "16") (name "16") (class "Default")
      (node (ref "M1") (pin "20") (pinfunction "CHAN11_20") (pintype "bidirectional"))
      (node (ref "RP16") (pin "2") (pinfunction "2_2") (pintype "passive"))
      (node (ref "SFH16") (pin "1") (pinfunction "K_1") (pintype "bidirectional"))
    )
    (net (code "17") (name "17") (class "Default")
      (node (ref "M1") (pin "21") (pinfunction "CHAN10_21") (pintype "bidirectional"))
      (node (ref "RP17") (pin "2") (pinfunction "2_2") (pintype "passive"))
      (node (ref "SFH17") (pin "1") (pinfunction "K_1") (pintype "bidirectional"))
    )
    (net (code "18") (name "18") (class "Default")
      (node (ref "M0") (pin "4") (pinfunction "CHAN5_4") (pintype "bidirectional"))
      (node (ref "RP18") (pin "2") (pinfunction "2_2") (pintype "passive"))
      (node (ref "SFH18") (pin "1") (pinfunction "K_1") (pintype "bidirectional"))
    )
    (net (code "19") (name "19") (class "Default")
      (node (ref "M0") (pin "5") (pinfunction "CHAN4_5") (pintype "bidirectional"))
      (node (ref "RP19") (pin "2") (pinfunction "2_2") (pintype "passive"))
      (node (ref "SFH19") (pin "1") (pinfunction "K_1") (pintype "bidirectional"))
    )
    (net (code "20") (name "21") (class "Default")
      (node (ref "M5") (pin "4") (pinfunction "CHAN5_4") (pintype "bidirectional"))
      (node (ref "RP21") (pin "2") (pinfunction "2_2") (pintype "passive"))
      (node (ref "SFH21") (pin "1") (pinfunction "K_1") (pintype "bidirectional"))
    )
    (net (code "21") (name "22") (class "Default")
      (node (ref "M1") (pin "7") (pinfunction "CHAN2_7") (pintype "bidirectional"))
      (node (ref "RP22") (pin "2") (pinfunction "2_2") (pintype "passive"))
      (node (ref "SFH22") (pin "1") (pinfunction "K_1") (pintype "bidirectional"))
    )
    (net (code "22") (name "23") (class "Default")
      (node (ref "M1") (pin "8") (pinfunction "CHAN1_8") (pintype "bidirectional"))
      (node (ref "RP23") (pin "2") (pinfunction "2_2") (pintype "passive"))
      (node (ref "SFH23") (pin "1") (pinfunction "K_1") (pintype "bidirectional"))
    )
    (net (code "23") (name "24") (class "Default")
      (node (ref "M1") (pin "9") (pinfunction "CHAN0_9") (pintype "bidirectional"))
      (node (ref "RP24") (pin "2") (pinfunction "2_2") (pintype "passive"))
      (node (ref "SFH24") (pin "1") (pinfunction "K_1") (pintype "bidirectional"))
    )
    (net (code "24") (name "25") (class "Default")
      (node (ref "M1") (pin "5") (pinfunction "CHAN4_5") (pintype "bidirectional"))
      (node (ref "RP25") (pin "2") (pinfunction "2_2") (pintype "passive"))
      (node (ref "SFH25") (pin "1") (pinfunction "K_1") (pintype "bidirectional"))
    )
    (net (code "25") (name "26") (class "Default")
      (node (ref "M1") (pin "3") (pinfunction "CHAN6_3") (pintype "bidirectional"))
      (node (ref "RP26") (pin "2") (pinfunction "2_2") (pintype "passive"))
      (node (ref "SFH26") (pin "1") (pinfunction "K_1") (pintype "bidirectional"))
    )
    (net (code "26") (name "27") (class "Default")
      (node (ref "M1") (pin "17") (pinfunction "CHAN14_17") (pintype "bidirectional"))
      (node (ref "RP27") (pin "2") (pinfunction "2_2") (pintype "passive"))
      (node (ref "SFH27") (pin "1") (pinfunction "K_1") (pintype "bidirectional"))
    )
    (net (code "27") (name "28") (class "Default")
      (node (ref "M1") (pin "19") (pinfunction "CHAN12_19") (pintype "bidirectional"))
      (node (ref "RP28") (pin "2") (pinfunction "2_2") (pintype "passive"))
      (node (ref "SFH28") (pin "1") (pinfunction "K_1") (pintype "bidirectional"))
    )
    (net (code "28") (name "29") (class "Default")
      (node (ref "M1") (pin "22") (pinfunction "CHAN9_22") (pintype "bidirectional"))
      (node (ref "RP29") (pin "2") (pinfunction "2_2") (pintype "passive"))
      (node (ref "SFH29") (pin "1") (pinfunction "K_1") (pintype "bidirectional"))
    )
    (net (code "29") (name "31") (class "Default")
      (node (ref "M5") (pin "23") (pinfunction "CHAN8_23") (pintype "bidirectional"))
      (node (ref "RP31") (pin "2") (pinfunction "2_2") (pintype "passive"))
      (node (ref "SFH31") (pin "1") (pinfunction "K_1") (pintype "bidirectional"))
    )
    (net (code "30") (name "32") (class "Default")
      (node (ref "M5") (pin "3") (pinfunction "CHAN6_3") (pintype "bidirectional"))
      (node (ref "RP32") (pin "2") (pinfunction "2_2") (pintype "passive"))
      (node (ref "SFH32") (pin "1") (pinfunction "K_1") (pintype "bidirectional"))
    )
    (net (code "31") (name "33") (class "Default")
      (node (ref "M4") (pin "22") (pinfunction "CHAN9_22") (pintype "bidirectional"))
      (node (ref "RP33") (pin "2") (pinfunction "2_2") (pintype "passive"))
      (node (ref "SFH33") (pin "1") (pinfunction "K_1") (pintype "bidirectional"))
    )
    (net (code "32") (name "34") (class "Default")
      (node (ref "M4") (pin "2") (pinfunction "CHAN7_2") (pintype "bidirectional"))
      (node (ref "RP34") (pin "2") (pinfunction "2_2") (pintype "passive"))
      (node (ref "SFH34") (pin "1") (pinfunction "K_1") (pintype "bidirectional"))
    )
    (net (code "33") (name "35") (class "Default")
      (node (ref "M4") (pin "4") (pinfunction "CHAN5_4") (pintype "bidirectional"))
      (node (ref "RP35") (pin "2") (pinfunction "2_2") (pintype "passive"))
      (node (ref "SFH35") (pin "1") (pinfunction "K_1") (pintype "bidirectional"))
    )
    (net (code "34") (name "36") (class "Default")
      (node (ref "M5") (pin "21") (pinfunction "CHAN10_21") (pintype "bidirectional"))
      (node (ref "RP36") (pin "2") (pinfunction "2_2") (pintype "passive"))
      (node (ref "SFH36") (pin "1") (pinfunction "K_1") (pintype "bidirectional"))
    )
    (net (code "35") (name "41") (class "Default")
      (node (ref "M3") (pin "8") (pinfunction "CHAN1_8") (pintype "bidirectional"))
      (node (ref "RP41") (pin "2") (pinfunction "2_2") (pintype "passive"))
      (node (ref "SFH41") (pin "1") (pinfunction "K_1") (pintype "bidirectional"))
    )
    (net (code "36") (name "42") (class "Default")
      (node (ref "M3") (pin "18") (pinfunction "CHAN13_18") (pintype "bidirectional"))
      (node (ref "RP42") (pin "2") (pinfunction "2_2") (pintype "passive"))
      (node (ref "SFH42") (pin "1") (pinfunction "K_1") (pintype "bidirectional"))
    )
    (net (code "37") (name "43") (class "Default")
      (node (ref "M5") (pin "17") (pinfunction "CHAN14_17") (pintype "bidirectional"))
      (node (ref "RP43") (pin "2") (pinfunction "2_2") (pintype "passive"))
      (node (ref "SFH43") (pin "1") (pinfunction "K_1") (pintype "bidirectional"))
    )
    (net (code "38") (name "44") (class "Default")
      (node (ref "M4") (pin "8") (pinfunction "CHAN1_8") (pintype "bidirectional"))
      (node (ref "RP44") (pin "2") (pinfunction "2_2") (pintype "passive"))
      (node (ref "SFH44") (pin "1") (pinfunction "K_1") (pintype "bidirectional"))
    )
    (net (code "39") (name "45") (class "Default")
      (node (ref "M2") (pin "7") (pinfunction "CHAN2_7") (pintype "bidirectional"))
      (node (ref "RP45") (pin "2") (pinfunction "2_2") (pintype "passive"))
      (node (ref "SFH45") (pin "1") (pinfunction "K_1") (pintype "bidirectional"))
    )
    (net (code "40") (name "46") (class "Default")
      (node (ref "M2") (pin "17") (pinfunction "CHAN14_17") (pintype "bidirectional"))
      (node (ref "RP46") (pin "2") (pinfunction "2_2") (pintype "passive"))
      (node (ref "SFH46") (pin "1") (pinfunction "K_1") (pintype "bidirectional"))
    )
    (net (code "41") (name "47") (class "Default")
      (node (ref "M2") (pin "16") (pinfunction "CHAN15_16") (pintype "bidirectional"))
      (node (ref "RP47") (pin "2") (pinfunction "2_2") (pintype "passive"))
      (node (ref "SFH47") (pin "1") (pinfunction "K_1") (pintype "bidirectional"))
    )
    (net (code "42") (name "48") (class "Default")
      (node (ref "M2") (pin "4") (pinfunction "CHAN5_4") (pintype "bidirectional"))
      (node (ref "RP48") (pin "2") (pinfunction "2_2") (pintype "passive"))
      (node (ref "SFH48") (pin "1") (pinfunction "K_1") (pintype "bidirectional"))
    )
    (net (code "43") (name "49") (class "Default")
      (node (ref "M2") (pin "8") (pinfunction "CHAN1_8") (pintype "bidirectional"))
      (node (ref "RP49") (pin "2") (pinfunction "2_2") (pintype "passive"))
      (node (ref "SFH49") (pin "1") (pinfunction "K_1") (pintype "bidirectional"))
    )
    (net (code "44") (name "51") (class "Default")
      (node (ref "M1") (pin "6") (pinfunction "CHAN3_6") (pintype "bidirectional"))
      (node (ref "RP51") (pin "2") (pinfunction "2_2") (pintype "passive"))
      (node (ref "SFH51") (pin "1") (pinfunction "K_1") (pintype "bidirectional"))
    )
    (net (code "45") (name "52") (class "Default")
      (node (ref "M1") (pin "4") (pinfunction "CHAN5_4") (pintype "bidirectional"))
      (node (ref "RP52") (pin "2") (pinfunction "2_2") (pintype "passive"))
      (node (ref "SFH52") (pin "1") (pinfunction "K_1") (pintype "bidirectional"))
    )
    (net (code "46") (name "53") (class "Default")
      (node (ref "M1") (pin "18") (pinfunction "CHAN13_18") (pintype "bidirectional"))
      (node (ref "RP53") (pin "2") (pinfunction "2_2") (pintype "passive"))
      (node (ref "SFH53") (pin "1") (pinfunction "K_1") (pintype "bidirectional"))
    )
    (net (code "47") (name "54") (class "Default")
      (node (ref "M0") (pin "2") (pinfunction "CHAN7_2") (pintype "bidirectional"))
      (node (ref "RP54") (pin "2") (pinfunction "2_2") (pintype "passive"))
      (node (ref "SFH54") (pin "1") (pinfunction "K_1") (pintype "bidirectional"))
    )
    (net (code "48") (name "55") (class "Default")
      (node (ref "M0") (pin "7") (pinfunction "CHAN2_7") (pintype "bidirectional"))
      (node (ref "RP55") (pin "2") (pinfunction "2_2") (pintype "passive"))
      (node (ref "SFH55") (pin "1") (pinfunction "K_1") (pintype "bidirectional"))
    )
    (net (code "49") (name "56") (class "Default")
      (node (ref "M0") (pin "21") (pinfunction "CHAN10_21") (pintype "bidirectional"))
      (node (ref "RP56") (pin "2") (pinfunction "2_2") (pintype "passive"))
      (node (ref "SFH56") (pin "1") (pinfunction "K_1") (pintype "bidirectional"))
    )
    (net (code "50") (name "57") (class "Default")
      (node (ref "M0") (pin "19") (pinfunction "CHAN12_19") (pintype "bidirectional"))
      (node (ref "RP57") (pin "2") (pinfunction "2_2") (pintype "passive"))
      (node (ref "SFH57") (pin "1") (pinfunction "K_1") (pintype "bidirectional"))
    )
    (net (code "51") (name "59") (class "Default")
      (node (ref "M4") (pin "6") (pinfunction "CHAN3_6") (pintype "bidirectional"))
      (node (ref "RP59") (pin "2") (pinfunction "2_2") (pintype "passive"))
      (node (ref "SFH59") (pin "1") (pinfunction "K_1") (pintype "bidirectional"))
    )
    (net (code "52") (name "110") (class "Default")
      (node (ref "M0") (pin "9") (pinfunction "CHAN0_9") (pintype "bidirectional"))
      (node (ref "RP110") (pin "2") (pinfunction "2_2") (pintype "passive"))
      (node (ref "SFH110") (pin "1") (pinfunction "K_1") (pintype "bidirectional"))
    )
    (net (code "53") (name "111") (class "Default")
      (node (ref "M0") (pin "23") (pinfunction "CHAN8_23") (pintype "bidirectional"))
      (node (ref "RP111") (pin "2") (pinfunction "2_2") (pintype "passive"))
      (node (ref "SFH111") (pin "1") (pinfunction "K_1") (pintype "bidirectional"))
    )
    (net (code "54") (name "112") (class "Default")
      (node (ref "M2") (pin "18") (pinfunction "CHAN13_18") (pintype "bidirectional"))
      (node (ref "RP112") (pin "2") (pinfunction "2_2") (pintype "passive"))
      (node (ref "SFH112") (pin "1") (pinfunction "K_1") (pintype "bidirectional"))
    )
    (net (code "55") (name "113") (class "Default")
      (node (ref "M2") (pin "19") (pinfunction "CHAN12_19") (pintype "bidirectional"))
      (node (ref "RP113") (pin "2") (pinfunction "2_2") (pintype "passive"))
      (node (ref "SFH113") (pin "1") (pinfunction "K_1") (pintype "bidirectional"))
    )
    (net (code "56") (name "114") (class "Default")
      (node (ref "M2") (pin "20") (pinfunction "CHAN11_20") (pintype "bidirectional"))
      (node (ref "RP114") (pin "2") (pinfunction "2_2") (pintype "passive"))
      (node (ref "SFH114") (pin "1") (pinfunction "K_1") (pintype "bidirectional"))
    )
    (net (code "57") (name "115") (class "Default")
      (node (ref "M2") (pin "21") (pinfunction "CHAN10_21") (pintype "bidirectional"))
      (node (ref "RP115") (pin "2") (pinfunction "2_2") (pintype "passive"))
      (node (ref "SFH115") (pin "1") (pinfunction "K_1") (pintype "bidirectional"))
    )
    (net (code "58") (name "116") (class "Default")
      (node (ref "M2") (pin "22") (pinfunction "CHAN9_22") (pintype "bidirectional"))
      (node (ref "RP116") (pin "2") (pinfunction "2_2") (pintype "passive"))
      (node (ref "SFH116") (pin "1") (pinfunction "K_1") (pintype "bidirectional"))
    )
    (net (code "59") (name "117") (class "Default")
      (node (ref "M2") (pin "23") (pinfunction "CHAN8_23") (pintype "bidirectional"))
      (node (ref "RP117") (pin "2") (pinfunction "2_2") (pintype "passive"))
      (node (ref "SFH117") (pin "1") (pinfunction "K_1") (pintype "bidirectional"))
    )
    (net (code "60") (name "118") (class "Default")
      (node (ref "M2") (pin "3") (pinfunction "CHAN6_3") (pintype "bidirectional"))
      (node (ref "RP118") (pin "2") (pinfunction "2_2") (pintype "passive"))
      (node (ref "SFH118") (pin "1") (pinfunction "K_1") (pintype "bidirectional"))
    )
    (net (code "61") (name "119") (class "Default")
      (node (ref "M2") (pin "2") (pinfunction "CHAN7_2") (pintype "bidirectional"))
      (node (ref "RP119") (pin "2") (pinfunction "2_2") (pintype "passive"))
      (node (ref "SFH119") (pin "1") (pinfunction "K_1") (pintype "bidirectional"))
    )
    (net (code "62") (name "120") (class "Default")
      (node (ref "M3") (pin "23") (pinfunction "CHAN8_23") (pintype "bidirectional"))
      (node (ref "RP120") (pin "2") (pinfunction "2_2") (pintype "passive"))
      (node (ref "SFH120") (pin "1") (pinfunction "K_1") (pintype "bidirectional"))
    )
    (net (code "63") (name "121") (class "Default")
      (node (ref "M3") (pin "22") (pinfunction "CHAN9_22") (pintype "bidirectional"))
      (node (ref "RP121") (pin "2") (pinfunction "2_2") (pintype "passive"))
      (node (ref "SFH121") (pin "1") (pinfunction "K_1") (pintype "bidirectional"))
    )
    (net (code "64") (name "122") (class "Default")
      (node (ref "M3") (pin "2") (pinfunction "CHAN7_2") (pintype "bidirectional"))
      (node (ref "RP122") (pin "2") (pinfunction "2_2") (pintype "passive"))
      (node (ref "SFH122") (pin "1") (pinfunction "K_1") (pintype "bidirectional"))
    )
    (net (code "65") (name "123") (class "Default")
      (node (ref "M3") (pin "3") (pinfunction "CHAN6_3") (pintype "bidirectional"))
      (node (ref "RP123") (pin "2") (pinfunction "2_2") (pintype "passive"))
      (node (ref "SFH123") (pin "1") (pinfunction "K_1") (pintype "bidirectional"))
    )
    (net (code "66") (name "124") (class "Default")
      (node (ref "M3") (pin "4") (pinfunction "CHAN5_4") (pintype "bidirectional"))
      (node (ref "RP124") (pin "2") (pinfunction "2_2") (pintype "passive"))
      (node (ref "SFH124") (pin "1") (pinfunction "K_1") (pintype "bidirectional"))
    )
    (net (code "67") (name "210") (class "Default")
      (node (ref "M0") (pin "3") (pinfunction "CHAN6_3") (pintype "bidirectional"))
      (node (ref "RP210") (pin "2") (pinfunction "2_2") (pintype "passive"))
      (node (ref "SFH210") (pin "1") (pinfunction "K_1") (pintype "bidirectional"))
    )
    (net (code "68") (name "211") (class "Default")
      (node (ref "M0") (pin "6") (pinfunction "CHAN3_6") (pintype "bidirectional"))
      (node (ref "RP211") (pin "2") (pinfunction "2_2") (pintype "passive"))
      (node (ref "SFH211") (pin "1") (pinfunction "K_1") (pintype "bidirectional"))
    )
    (net (code "69") (name "212") (class "Default")
      (node (ref "M0") (pin "8") (pinfunction "CHAN1_8") (pintype "bidirectional"))
      (node (ref "RP212") (pin "2") (pinfunction "2_2") (pintype "passive"))
      (node (ref "SFH212") (pin "1") (pinfunction "K_1") (pintype "bidirectional"))
    )
    (net (code "70") (name "213") (class "Default")
      (node (ref "M0") (pin "22") (pinfunction "CHAN9_22") (pintype "bidirectional"))
      (node (ref "RP213") (pin "2") (pinfunction "2_2") (pintype "passive"))
      (node (ref "SFH213") (pin "1") (pinfunction "K_1") (pintype "bidirectional"))
    )
    (net (code "71") (name "214") (class "Default")
      (node (ref "M0") (pin "20") (pinfunction "CHAN11_20") (pintype "bidirectional"))
      (node (ref "RP214") (pin "2") (pinfunction "2_2") (pintype "passive"))
      (node (ref "SFH214") (pin "1") (pinfunction "K_1") (pintype "bidirectional"))
    )
    (net (code "72") (name "215") (class "Default")
      (node (ref "M0") (pin "16") (pinfunction "CHAN15_16") (pintype "bidirectional"))
      (node (ref "RP215") (pin "2") (pinfunction "2_2") (pintype "passive"))
      (node (ref "SFH215") (pin "1") (pinfunction "K_1") (pintype "bidirectional"))
    )
    (net (code "73") (name "216") (class "Default")
      (node (ref "M0") (pin "17") (pinfunction "CHAN14_17") (pintype "bidirectional"))
      (node (ref "RP216") (pin "2") (pinfunction "2_2") (pintype "passive"))
      (node (ref "SFH216") (pin "1") (pinfunction "K_1") (pintype "bidirectional"))
    )
    (net (code "74") (name "217") (class "Default")
      (node (ref "M0") (pin "18") (pinfunction "CHAN13_18") (pintype "bidirectional"))
      (node (ref "RP217") (pin "2") (pinfunction "2_2") (pintype "passive"))
      (node (ref "SFH217") (pin "1") (pinfunction "K_1") (pintype "bidirectional"))
    )
    (net (code "75") (name "218") (class "Default")
      (node (ref "M4") (pin "21") (pinfunction "CHAN10_21") (pintype "bidirectional"))
      (node (ref "RP218") (pin "2") (pinfunction "2_2") (pintype "passive"))
      (node (ref "SFH218") (pin "1") (pinfunction "K_1") (pintype "bidirectional"))
    )
    (net (code "76") (name "219") (class "Default")
      (node (ref "M4") (pin "20") (pinfunction "CHAN11_20") (pintype "bidirectional"))
      (node (ref "RP219") (pin "2") (pinfunction "2_2") (pintype "passive"))
      (node (ref "SFH219") (pin "1") (pinfunction "K_1") (pintype "bidirectional"))
    )
    (net (code "77") (name "220") (class "Default")
      (node (ref "M4") (pin "19") (pinfunction "CHAN12_19") (pintype "bidirectional"))
      (node (ref "RP220") (pin "2") (pinfunction "2_2") (pintype "passive"))
      (node (ref "SFH220") (pin "1") (pinfunction "K_1") (pintype "bidirectional"))
    )
    (net (code "78") (name "221") (class "Default")
      (node (ref "M4") (pin "18") (pinfunction "CHAN13_18") (pintype "bidirectional"))
      (node (ref "RP221") (pin "2") (pinfunction "2_2") (pintype "passive"))
      (node (ref "SFH221") (pin "1") (pinfunction "K_1") (pintype "bidirectional"))
    )
    (net (code "79") (name "222") (class "Default")
      (node (ref "M4") (pin "17") (pinfunction "CHAN14_17") (pintype "bidirectional"))
      (node (ref "RP222") (pin "2") (pinfunction "2_2") (pintype "passive"))
      (node (ref "SFH222") (pin "1") (pinfunction "K_1") (pintype "bidirectional"))
    )
    (net (code "80") (name "223") (class "Default")
      (node (ref "M4") (pin "16") (pinfunction "CHAN15_16") (pintype "bidirectional"))
      (node (ref "RP223") (pin "2") (pinfunction "2_2") (pintype "passive"))
      (node (ref "SFH223") (pin "1") (pinfunction "K_1") (pintype "bidirectional"))
    )
    (net (code "81") (name "224") (class "Default")
      (node (ref "M4") (pin "3") (pinfunction "CHAN6_3") (pintype "bidirectional"))
      (node (ref "RP224") (pin "2") (pinfunction "2_2") (pintype "passive"))
      (node (ref "SFH224") (pin "1") (pinfunction "K_1") (pintype "bidirectional"))
    )
    (net (code "82") (name "225") (class "Default")
      (node (ref "M4") (pin "5") (pinfunction "CHAN4_5") (pintype "bidirectional"))
      (node (ref "RP225") (pin "2") (pinfunction "2_2") (pintype "passive"))
      (node (ref "SFH225") (pin "1") (pinfunction "K_1") (pintype "bidirectional"))
    )
    (net (code "83") (name "226") (class "Default")
      (node (ref "M5") (pin "19") (pinfunction "CHAN12_19") (pintype "bidirectional"))
      (node (ref "RP226") (pin "2") (pinfunction "2_2") (pintype "passive"))
      (node (ref "SFH226") (pin "1") (pinfunction "K_1") (pintype "bidirectional"))
    )
    (net (code "84") (name "227") (class "Default")
      (node (ref "M5") (pin "22") (pinfunction "CHAN9_22") (pintype "bidirectional"))
      (node (ref "RP227") (pin "2") (pinfunction "2_2") (pintype "passive"))
      (node (ref "SFH227") (pin "1") (pinfunction "K_1") (pintype "bidirectional"))
    )
    (net (code "85") (name "228") (class "Default")
      (node (ref "M5") (pin "9") (pinfunction "CHAN0_9") (pintype "bidirectional"))
      (node (ref "RP228") (pin "2") (pinfunction "2_2") (pintype "passive"))
      (node (ref "SFH228") (pin "1") (pinfunction "K_1") (pintype "bidirectional"))
    )
    (net (code "86") (name "229") (class "Default")
      (node (ref "M5") (pin "8") (pinfunction "CHAN1_8") (pintype "bidirectional"))
      (node (ref "RP229") (pin "2") (pinfunction "2_2") (pintype "passive"))
      (node (ref "SFH229") (pin "1") (pinfunction "K_1") (pintype "bidirectional"))
    )
    (net (code "87") (name "230") (class "Default")
      (node (ref "M5") (pin "7") (pinfunction "CHAN2_7") (pintype "bidirectional"))
      (node (ref "RP230") (pin "2") (pinfunction "2_2") (pintype "passive"))
      (node (ref "SFH230") (pin "1") (pinfunction "K_1") (pintype "bidirectional"))
    )
    (net (code "88") (name "231") (class "Default")
      (node (ref "M5") (pin "6") (pinfunction "CHAN3_6") (pintype "bidirectional"))
      (node (ref "RP231") (pin "2") (pinfunction "2_2") (pintype "passive"))
      (node (ref "SFH231") (pin "1") (pinfunction "K_1") (pintype "bidirectional"))
    )
    (net (code "89") (name "232") (class "Default")
      (node (ref "M5") (pin "5") (pinfunction "CHAN4_5") (pintype "bidirectional"))
      (node (ref "RP232") (pin "2") (pinfunction "2_2") (pintype "passive"))
      (node (ref "SFH232") (pin "1") (pinfunction "K_1") (pintype "bidirectional"))
    )
    (net (code "90") (name "410") (class "Default")
      (node (ref "M3") (pin "17") (pinfunction "CHAN14_17") (pintype "bidirectional"))
      (node (ref "RP410") (pin "2") (pinfunction "2_2") (pintype "passive"))
      (node (ref "SFH410") (pin "1") (pinfunction "K_1") (pintype "bidirectional"))
    )
    (net (code "91") (name "411") (class "Default")
      (node (ref "M3") (pin "21") (pinfunction "CHAN10_21") (pintype "bidirectional"))
      (node (ref "RP411") (pin "2") (pinfunction "2_2") (pintype "passive"))
      (node (ref "SFH411") (pin "1") (pinfunction "K_1") (pintype "bidirectional"))
    )
    (net (code "92") (name "412") (class "Default")
      (node (ref "M3") (pin "9") (pinfunction "CHAN0_9") (pintype "bidirectional"))
      (node (ref "RP412") (pin "2") (pinfunction "2_2") (pintype "passive"))
      (node (ref "SFH412") (pin "1") (pinfunction "K_1") (pintype "bidirectional"))
    )
    (net (code "93") (name "510") (class "Default")
      (node (ref "M4") (pin "7") (pinfunction "CHAN2_7") (pintype "bidirectional"))
      (node (ref "RP510") (pin "2") (pinfunction "2_2") (pintype "passive"))
      (node (ref "SFH510") (pin "1") (pinfunction "K_1") (pintype "bidirectional"))
    )
    (net (code "94") (name "511") (class "Default")
      (node (ref "M5") (pin "18") (pinfunction "CHAN13_18") (pintype "bidirectional"))
      (node (ref "RP511") (pin "2") (pinfunction "2_2") (pintype "passive"))
      (node (ref "SFH511") (pin "1") (pinfunction "K_1") (pintype "bidirectional"))
    )
    (net (code "95") (name "GND") (class "Default")
      (node (ref "JP2") (pin "1") (pinfunction "1_1") (pintype "passive"))
      (node (ref "LED01") (pin "123") (pinfunction "GND_123") (pintype "bidirectional"))
      (node (ref "LED02") (pin "123") (pinfunction "GND_123") (pintype "bidirectional"))
      (node (ref "LED03") (pin "123") (pinfunction "GND_123") (pintype "bidirectional"))
      (node (ref "LED04") (pin "123") (pinfunction "GND_123") (pintype "bidirectional"))
      (node (ref "LED11") (pin "123") (pinfunction "GND_123") (pintype "bidirectional"))
      (node (ref "LED110") (pin "123") (pinfunction "GND_123") (pintype "bidirectional"))
      (node (ref "LED111") (pin "123") (pinfunction "GND_123") (pintype "bidirectional"))
      (node (ref "LED112") (pin "123") (pinfunction "GND_123") (pintype "bidirectional"))
      (node (ref "LED12") (pin "123") (pinfunction "GND_123") (pintype "bidirectional"))
      (node (ref "LED13") (pin "123") (pinfunction "GND_123") (pintype "bidirectional"))
      (node (ref "LED14") (pin "123") (pinfunction "GND_123") (pintype "bidirectional"))
      (node (ref "LED15") (pin "123") (pinfunction "GND_123") (pintype "bidirectional"))
      (node (ref "LED16") (pin "123") (pinfunction "GND_123") (pintype "bidirectional"))
      (node (ref "LED17") (pin "123") (pinfunction "GND_123") (pintype "bidirectional"))
      (node (ref "LED18") (pin "123") (pinfunction "GND_123") (pintype "bidirectional"))
      (node (ref "LED19") (pin "123") (pinfunction "GND_123") (pintype "bidirectional"))
      (node (ref "LED21") (pin "123") (pinfunction "GND_123") (pintype "bidirectional"))
      (node (ref "LED210") (pin "123") (pinfunction "GND_123") (pintype "bidirectional"))
      (node (ref "LED211") (pin "123") (pinfunction "GND_123") (pintype "bidirectional"))
      (node (ref "LED212") (pin "123") (pinfunction "GND_123") (pintype "bidirectional"))
      (node (ref "LED213") (pin "123") (pinfunction "GND_123") (pintype "bidirectional"))
      (node (ref "LED214") (pin "123") (pinfunction "GND_123") (pintype "bidirectional"))
      (node (ref "LED215") (pin "123") (pinfunction "GND_123") (pintype "bidirectional"))
      (node (ref "LED216") (pin "123") (pinfunction "GND_123") (pintype "bidirectional"))
      (node (ref "LED22") (pin "123") (pinfunction "GND_123") (pintype "bidirectional"))
      (node (ref "LED23") (pin "123") (pinfunction "GND_123") (pintype "bidirectional"))
      (node (ref "LED24") (pin "123") (pinfunction "GND_123") (pintype "bidirectional"))
      (node (ref "LED25") (pin "123") (pinfunction "GND_123") (pintype "bidirectional"))
      (node (ref "LED26") (pin "123") (pinfunction "GND_123") (pintype "bidirectional"))
      (node (ref "LED27") (pin "123") (pinfunction "GND_123") (pintype "bidirectional"))
      (node (ref "LED28") (pin "123") (pinfunction "GND_123") (pintype "bidirectional"))
      (node (ref "LED29") (pin "123") (pinfunction "GND_123") (pintype "bidirectional"))
      (node (ref "LED31") (pin "123") (pinfunction "GND_123") (pintype "bidirectional"))
      (node (ref "LED32") (pin "123") (pinfunction "GND_123") (pintype "bidirectional"))
      (node (ref "LED33") (pin "123") (pinfunction "GND_123") (pintype "bidirectional"))
      (node (ref "M0") (pin "12") (pinfunction "GND_12") (pintype "bidirectional"))
      (node (ref "M0") (pin "15") (pinfunction "EN_15") (pintype "input"))
      (node (ref "M1") (pin "12") (pinfunction "GND_12") (pintype "bidirectional"))
      (node (ref "M1") (pin "15") (pinfunction "EN_15") (pintype "input"))
      (node (ref "M2") (pin "12") (pinfunction "GND_12") (pintype "bidirectional"))
      (node (ref "M2") (pin "15") (pinfunction "EN_15") (pintype "input"))
      (node (ref "M3") (pin "12") (pinfunction "GND_12") (pintype "bidirectional"))
      (node (ref "M3") (pin "15") (pinfunction "EN_15") (pintype "input"))
      (node (ref "M4") (pin "12") (pinfunction "GND_12") (pintype "bidirectional"))
      (node (ref "M4") (pin "15") (pinfunction "EN_15") (pintype "input"))
      (node (ref "M5") (pin "12") (pinfunction "GND_12") (pintype "bidirectional"))
      (node (ref "M5") (pin "15") (pinfunction "EN_15") (pintype "input"))
      (node (ref "R08") (pin "1") (pinfunction "1_1") (pintype "passive"))
      (node (ref "R09") (pin "1") (pinfunction "1_1") (pintype "passive"))
      (node (ref "R32") (pin "1") (pinfunction "1_1") (pintype "passive"))
      (node (ref "R33") (pin "1") (pinfunction "1_1") (pintype "passive"))
      (node (ref "R34") (pin "1") (pinfunction "1_1") (pintype "passive"))
      (node (ref "R35") (pin "1") (pinfunction "1_1") (pintype "passive"))
      (node (ref "R42") (pin "1") (pinfunction "1_1") (pintype "passive"))
      (node (ref "R43") (pin "1") (pinfunction "1_1") (pintype "passive"))
      (node (ref "R58") (pin "1") (pinfunction "1_1") (pintype "passive"))
      (node (ref "RP01") (pin "1") (pinfunction "1_1") (pintype "passive"))
      (node (ref "RP02") (pin "1") (pinfunction "1_1") (pintype "passive"))
      (node (ref "RP03") (pin "1") (pinfunction "1_1") (pintype "passive"))
      (node (ref "RP04") (pin "1") (pinfunction "1_1") (pintype "passive"))
      (node (ref "RP05") (pin "1") (pinfunction "1_1") (pintype "passive"))
      (node (ref "RP06") (pin "1") (pinfunction "1_1") (pintype "passive"))
      (node (ref "RP07") (pin "1") (pinfunction "1_1") (pintype "passive"))
      (node (ref "RP08") (pin "1") (pinfunction "1_1") (pintype "passive"))
      (node (ref "RP11") (pin "1") (pinfunction "1_1") (pintype "passive"))
      (node (ref "RP110") (pin "1") (pinfunction "1_1") (pintype "passive"))
      (node (ref "RP111") (pin "1") (pinfunction "1_1") (pintype "passive"))
      (node (ref "RP112") (pin "1") (pinfunction "1_1") (pintype "passive"))
      (node (ref "RP113") (pin "1") (pinfunction "1_1") (pintype "passive"))
      (node (ref "RP114") (pin "1") (pinfunction "1_1") (pintype "passive"))
      (node (ref "RP115") (pin "1") (pinfunction "1_1") (pintype "passive"))
      (node (ref "RP116") (pin "1") (pinfunction "1_1") (pintype "passive"))
      (node (ref "RP117") (pin "1") (pinfunction "1_1") (pintype "passive"))
      (node (ref "RP118") (pin "1") (pinfunction "1_1") (pintype "passive"))
      (node (ref "RP119") (pin "1") (pinfunction "1_1") (pintype "passive"))
      (node (ref "RP12") (pin "1") (pinfunction "1_1") (pintype "passive"))
      (node (ref "RP120") (pin "1") (pinfunction "1_1") (pintype "passive"))
      (node (ref "RP121") (pin "1") (pinfunction "1_1") (pintype "passive"))
      (node (ref "RP122") (pin "1") (pinfunction "1_1") (pintype "passive"))
      (node (ref "RP123") (pin "1") (pinfunction "1_1") (pintype "passive"))
      (node (ref "RP124") (pin "1") (pinfunction "1_1") (pintype "passive"))
      (node (ref "RP13") (pin "1") (pinfunction "1_1") (pintype "passive"))
      (node (ref "RP14") (pin "1") (pinfunction "1_1") (pintype "passive"))
      (node (ref "RP15") (pin "1") (pinfunction "1_1") (pintype "passive"))
      (node (ref "RP16") (pin "1") (pinfunction "1_1") (pintype "passive"))
      (node (ref "RP17") (pin "1") (pinfunction "1_1") (pintype "passive"))
      (node (ref "RP18") (pin "1") (pinfunction "1_1") (pintype "passive"))
      (node (ref "RP19") (pin "1") (pinfunction "1_1") (pintype "passive"))
      (node (ref "RP21") (pin "1") (pinfunction "1_1") (pintype "passive"))
      (node (ref "RP210") (pin "1") (pinfunction "1_1") (pintype "passive"))
      (node (ref "RP211") (pin "1") (pinfunction "1_1") (pintype "passive"))
      (node (ref "RP212") (pin "1") (pinfunction "1_1") (pintype "passive"))
      (node (ref "RP213") (pin "1") (pinfunction "1_1") (pintype "passive"))
      (node (ref "RP214") (pin "1") (pinfunction "1_1") (pintype "passive"))
      (node (ref "RP215") (pin "1") (pinfunction "1_1") (pintype "passive"))
      (node (ref "RP216") (pin "1") (pinfunction "1_1") (pintype "passive"))
      (node (ref "RP217") (pin "1") (pinfunction "1_1") (pintype "passive"))
      (node (ref "RP218") (pin "1") (pinfunction "1_1") (pintype "passive"))
      (node (ref "RP219") (pin "1") (pinfunction "1_1") (pintype "passive"))
      (node (ref "RP22") (pin "1") (pinfunction "1_1") (pintype "passive"))
      (node (ref "RP220") (pin "1") (pinfunction "1_1") (pintype "passive"))
      (node (ref "RP221") (pin "1") (pinfunction "1_1") (pintype "passive"))
      (node (ref "RP222") (pin "1") (pinfunction "1_1") (pintype "passive"))
      (node (ref "RP223") (pin "1") (pinfunction "1_1") (pintype "passive"))
      (node (ref "RP224") (pin "1") (pinfunction "1_1") (pintype "passive"))
      (node (ref "RP225") (pin "1") (pinfunction "1_1") (pintype "passive"))
      (node (ref "RP226") (pin "1") (pinfunction "1_1") (pintype "passive"))
      (node (ref "RP227") (pin "1") (pinfunction "1_1") (pintype "passive"))
      (node (ref "RP228") (pin "1") (pinfunction "1_1") (pintype "passive"))
      (node (ref "RP229") (pin "1") (pinfunction "1_1") (pintype "passive"))
      (node (ref "RP23") (pin "1") (pinfunction "1_1") (pintype "passive"))
      (node (ref "RP230") (pin "1") (pinfunction "1_1") (pintype "passive"))
      (node (ref "RP231") (pin "1") (pinfunction "1_1") (pintype "passive"))
      (node (ref "RP232") (pin "1") (pinfunction "1_1") (pintype "passive"))
      (node (ref "RP24") (pin "1") (pinfunction "1_1") (pintype "passive"))
      (node (ref "RP25") (pin "1") (pinfunction "1_1") (pintype "passive"))
      (node (ref "RP26") (pin "1") (pinfunction "1_1") (pintype "passive"))
      (node (ref "RP27") (pin "1") (pinfunction "1_1") (pintype "passive"))
      (node (ref "RP28") (pin "1") (pinfunction "1_1") (pintype "passive"))
      (node (ref "RP29") (pin "1") (pinfunction "1_1") (pintype "passive"))
      (node (ref "RP31") (pin "1") (pinfunction "1_1") (pintype "passive"))
      (node (ref "RP32") (pin "1") (pinfunction "1_1") (pintype "passive"))
      (node (ref "RP33") (pin "1") (pinfunction "1_1") (pintype "passive"))
      (node (ref "RP34") (pin "1") (pinfunction "1_1") (pintype "passive"))
      (node (ref "RP35") (pin "1") (pinfunction "1_1") (pintype "passive"))
      (node (ref "RP36") (pin "1") (pinfunction "1_1") (pintype "passive"))
      (node (ref "RP41") (pin "1") (pinfunction "1_1") (pintype "passive"))
      (node (ref "RP410") (pin "1") (pinfunction "1_1") (pintype "passive"))
      (node (ref "RP411") (pin "1") (pinfunction "1_1") (pintype "passive"))
      (node (ref "RP412") (pin "1") (pinfunction "1_1") (pintype "passive"))
      (node (ref "RP42") (pin "1") (pinfunction "1_1") (pintype "passive"))
      (node (ref "RP43") (pin "1") (pinfunction "1_1") (pintype "passive"))
      (node (ref "RP44") (pin "1") (pinfunction "1_1") (pintype "passive"))
      (node (ref "RP45") (pin "1") (pinfunction "1_1") (pintype "passive"))
      (node (ref "RP46") (pin "1") (pinfunction "1_1") (pintype "passive"))
      (node (ref "RP47") (pin "1") (pinfunction "1_1") (pintype "passive"))
      (node (ref "RP48") (pin "1") (pinfunction "1_1") (pintype "passive"))
      (node (ref "RP49") (pin "1") (pinfunction "1_1") (pintype "passive"))
      (node (ref "RP51") (pin "1") (pinfunction "1_1") (pintype "passive"))
      (node (ref "RP510") (pin "1") (pinfunction "1_1") (pintype "passive"))
      (node (ref "RP511") (pin "1") (pinfunction "1_1") (pintype "passive"))
      (node (ref "RP52") (pin "1") (pinfunction "1_1") (pintype "passive"))
      (node (ref "RP53") (pin "1") (pinfunction "1_1") (pintype "passive"))
      (node (ref "RP54") (pin "1") (pinfunction "1_1") (pintype "passive"))
      (node (ref "RP55") (pin "1") (pinfunction "1_1") (pintype "passive"))
      (node (ref "RP56") (pin "1") (pinfunction "1_1") (pintype "passive"))
      (node (ref "RP57") (pin "1") (pinfunction "1_1") (pintype "passive"))
      (node (ref "RP59") (pin "1") (pinfunction "1_1") (pintype "passive"))
    )
    (net (code "96") (name "IR1") (class "Default")
      (node (ref "M1") (pin "23") (pinfunction "CHAN8_23") (pintype "bidirectional"))
      (node (ref "Q2") (pin "2") (pinfunction "E_2") (pintype "bidirectional"))
      (node (ref "R42") (pin "2") (pinfunction "2_2") (pintype "passive"))
    )
    (net (code "97") (name "IR2") (class "Default")
      (node (ref "M5") (pin "20") (pinfunction "CHAN11_20") (pintype "bidirectional"))
      (node (ref "Q1") (pin "2") (pinfunction "E_2") (pintype "bidirectional"))
      (node (ref "R08") (pin "2") (pinfunction "2_2") (pintype "passive"))
    )
    (net (code "98") (name "IR3") (class "Default")
      (node (ref "M5") (pin "2") (pinfunction "CHAN7_2") (pintype "bidirectional"))
      (node (ref "Q5") (pin "2") (pinfunction "E_2") (pintype "bidirectional"))
      (node (ref "R32") (pin "2") (pinfunction "2_2") (pintype "passive"))
    )
    (net (code "99") (name "IR4") (class "Default")
      (node (ref "M4") (pin "23") (pinfunction "CHAN8_23") (pintype "bidirectional"))
      (node (ref "Q6") (pin "2") (pinfunction "E_2") (pintype "bidirectional"))
      (node (ref "R34") (pin "2") (pinfunction "2_2") (pintype "passive"))
    )
    (net (code "100") (name "Net-(LED01-+3V3)") (class "Default")
      (node (ref "LED01") (pin "456") (pinfunction "+3V3_456") (pintype "bidirectional"))
      (node (ref "R01") (pin "1") (pinfunction "1_1") (pintype "passive"))
    )
    (net (code "101") (name "Net-(LED02-+3V3)") (class "Default")
      (node (ref "LED02") (pin "456") (pinfunction "+3V3_456") (pintype "bidirectional"))
      (node (ref "R02") (pin "1") (pinfunction "1_1") (pintype "passive"))
    )
    (net (code "102") (name "Net-(LED03-+3V3)") (class "Default")
      (node (ref "LED03") (pin "456") (pinfunction "+3V3_456") (pintype "bidirectional"))
      (node (ref "R03") (pin "1") (pinfunction "1_1") (pintype "passive"))
    )
    (net (code "103") (name "Net-(LED04-+3V3)") (class "Default")
      (node (ref "LED04") (pin "456") (pinfunction "+3V3_456") (pintype "bidirectional"))
      (node (ref "R04") (pin "1") (pinfunction "1_1") (pintype "passive"))
    )
    (net (code "104") (name "Net-(LED5-K)") (class "Default")
      (node (ref "LED5") (pin "2") (pinfunction "K_2") (pintype "bidirectional"))
      (node (ref "R43") (pin "2") (pinfunction "2_2") (pintype "passive"))
    )
    (net (code "105") (name "Net-(LED06-K)") (class "Default")
      (node (ref "LED06") (pin "2") (pinfunction "K_2") (pintype "bidirectional"))
      (node (ref "R09") (pin "2") (pinfunction "2_2") (pintype "passive"))
    )
    (net (code "106") (name "Net-(LED09-K)") (class "Default")
      (node (ref "LED09") (pin "2") (pinfunction "K_2") (pintype "bidirectional"))
      (node (ref "R33") (pin "2") (pinfunction "2_2") (pintype "passive"))
    )
    (net (code "107") (name "Net-(LED10-K)") (class "Default")
      (node (ref "LED10") (pin "2") (pinfunction "K_2") (pintype "bidirectional"))
      (node (ref "R35") (pin "2") (pinfunction "2_2") (pintype "passive"))
    )
    (net (code "108") (name "Net-(LED11-+3V3)") (class "Default")
      (node (ref "LED11") (pin "456") (pinfunction "+3V3_456") (pintype "bidirectional"))
      (node (ref "R11") (pin "1") (pinfunction "1_1") (pintype "passive"))
    )
    (net (code "109") (name "Net-(LED12-+3V3)") (class "Default")
      (node (ref "LED12") (pin "456") (pinfunction "+3V3_456") (pintype "bidirectional"))
      (node (ref "R12") (pin "1") (pinfunction "1_1") (pintype "passive"))
    )
    (net (code "110") (name "Net-(LED13-+3V3)") (class "Default")
      (node (ref "LED13") (pin "456") (pinfunction "+3V3_456") (pintype "bidirectional"))
      (node (ref "R13") (pin "1") (pinfunction "1_1") (pintype "passive"))
    )
    (net (code "111") (name "Net-(LED14-+3V3)") (class "Default")
      (node (ref "LED14") (pin "456") (pinfunction "+3V3_456") (pintype "bidirectional"))
      (node (ref "R14") (pin "1") (pinfunction "1_1") (pintype "passive"))
    )
    (net (code "112") (name "Net-(LED15-+3V3)") (class "Default")
      (node (ref "LED15") (pin "456") (pinfunction "+3V3_456") (pintype "bidirectional"))
      (node (ref "R15") (pin "1") (pinfunction "1_1") (pintype "passive"))
    )
    (net (code "113") (name "Net-(LED16-+3V3)") (class "Default")
      (node (ref "LED16") (pin "456") (pinfunction "+3V3_456") (pintype "bidirectional"))
      (node (ref "R16") (pin "1") (pinfunction "1_1") (pintype "passive"))
    )
    (net (code "114") (name "Net-(LED17-+3V3)") (class "Default")
      (node (ref "LED17") (pin "456") (pinfunction "+3V3_456") (pintype "bidirectional"))
      (node (ref "R17") (pin "1") (pinfunction "1_1") (pintype "passive"))
    )
    (net (code "115") (name "Net-(LED18-+3V3)") (class "Default")
      (node (ref "LED18") (pin "456") (pinfunction "+3V3_456") (pintype "bidirectional"))
      (node (ref "R18") (pin "1") (pinfunction "1_1") (pintype "passive"))
    )
    (net (code "116") (name "Net-(LED19-+3V3)") (class "Default")
      (node (ref "LED19") (pin "456") (pinfunction "+3V3_456") (pintype "bidirectional"))
      (node (ref "R19") (pin "1") (pinfunction "1_1") (pintype "passive"))
    )
    (net (code "117") (name "Net-(LED21-+3V3)") (class "Default")
      (node (ref "LED21") (pin "456") (pinfunction "+3V3_456") (pintype "bidirectional"))
      (node (ref "R21") (pin "1") (pinfunction "1_1") (pintype "passive"))
    )
    (net (code "118") (name "Net-(LED22-+3V3)") (class "Default")
      (node (ref "LED22") (pin "456") (pinfunction "+3V3_456") (pintype "bidirectional"))
      (node (ref "R22") (pin "1") (pinfunction "1_1") (pintype "passive"))
    )
    (net (code "119") (name "Net-(LED23-+3V3)") (class "Default")
      (node (ref "LED23") (pin "456") (pinfunction "+3V3_456") (pintype "bidirectional"))
      (node (ref "R23") (pin "1") (pinfunction "1_1") (pintype "passive"))
    )
    (net (code "120") (name "Net-(LED24-+3V3)") (class "Default")
      (node (ref "LED24") (pin "456") (pinfunction "+3V3_456") (pintype "bidirectional"))
      (node (ref "R24") (pin "1") (pinfunction "1_1") (pintype "passive"))
    )
    (net (code "121") (name "Net-(LED25-+3V3)") (class "Default")
      (node (ref "LED25") (pin "456") (pinfunction "+3V3_456") (pintype "bidirectional"))
      (node (ref "R25") (pin "1") (pinfunction "1_1") (pintype "passive"))
    )
    (net (code "122") (name "Net-(LED26-+3V3)") (class "Default")
      (node (ref "LED26") (pin "456") (pinfunction "+3V3_456") (pintype "bidirectional"))
      (node (ref "R26") (pin "1") (pinfunction "1_1") (pintype "passive"))
    )
    (net (code "123") (name "Net-(LED27-+3V3)") (class "Default")
      (node (ref "LED27") (pin "456") (pinfunction "+3V3_456") (pintype "bidirectional"))
      (node (ref "R27") (pin "1") (pinfunction "1_1") (pintype "passive"))
    )
    (net (code "124") (name "Net-(LED28-+3V3)") (class "Default")
      (node (ref "LED28") (pin "456") (pinfunction "+3V3_456") (pintype "bidirectional"))
      (node (ref "R28") (pin "1") (pinfunction "1_1") (pintype "passive"))
    )
    (net (code "125") (name "Net-(LED29-+3V3)") (class "Default")
      (node (ref "LED29") (pin "456") (pinfunction "+3V3_456") (pintype "bidirectional"))
      (node (ref "R29") (pin "1") (pinfunction "1_1") (pintype "passive"))
    )
    (net (code "126") (name "Net-(LED31-+3V3)") (class "Default")
      (node (ref "LED31") (pin "456") (pinfunction "+3V3_456") (pintype "bidirectional"))
      (node (ref "R05") (pin "1") (pinfunction "1_1") (pintype "passive"))
    )
    (net (code "127") (name "Net-(LED32-+3V3)") (class "Default")
      (node (ref "LED32") (pin "456") (pinfunction "+3V3_456") (pintype "bidirectional"))
      (node (ref "R06") (pin "1") (pinfunction "1_1") (pintype "passive"))
    )
    (net (code "128") (name "Net-(LED33-+3V3)") (class "Default")
      (node (ref "LED33") (pin "456") (pinfunction "+3V3_456") (pintype "bidirectional"))
      (node (ref "R07") (pin "1") (pinfunction "1_1") (pintype "passive"))
    )
    (net (code "129") (name "Net-(LED41-PadC)") (class "Default")
      (node (ref "LED41") (pin "C") (pinfunction "C_C") (pintype "passive"))
      (node (ref "R58") (pin "2") (pinfunction "2_2") (pintype "passive"))
    )
    (net (code "130") (name "Net-(LED110-+3V3)") (class "Default")
      (node (ref "LED110") (pin "456") (pinfunction "+3V3_456") (pintype "bidirectional"))
      (node (ref "R110") (pin "1") (pinfunction "1_1") (pintype "passive"))
    )
    (net (code "131") (name "Net-(LED111-+3V3)") (class "Default")
      (node (ref "LED111") (pin "456") (pinfunction "+3V3_456") (pintype "bidirectional"))
      (node (ref "R111") (pin "1") (pinfunction "1_1") (pintype "passive"))
    )
    (net (code "132") (name "Net-(LED112-+3V3)") (class "Default")
      (node (ref "LED112") (pin "456") (pinfunction "+3V3_456") (pintype "bidirectional"))
      (node (ref "R112") (pin "1") (pinfunction "1_1") (pintype "passive"))
    )
    (net (code "133") (name "Net-(LED210-+3V3)") (class "Default")
      (node (ref "LED210") (pin "456") (pinfunction "+3V3_456") (pintype "bidirectional"))
      (node (ref "R210") (pin "1") (pinfunction "1_1") (pintype "passive"))
    )
    (net (code "134") (name "Net-(LED211-+3V3)") (class "Default")
      (node (ref "LED211") (pin "456") (pinfunction "+3V3_456") (pintype "bidirectional"))
      (node (ref "R211") (pin "1") (pinfunction "1_1") (pintype "passive"))
    )
    (net (code "135") (name "Net-(LED212-+3V3)") (class "Default")
      (node (ref "LED212") (pin "456") (pinfunction "+3V3_456") (pintype "bidirectional"))
      (node (ref "R212") (pin "1") (pinfunction "1_1") (pintype "passive"))
    )
    (net (code "136") (name "Net-(LED213-+3V3)") (class "Default")
      (node (ref "LED213") (pin "456") (pinfunction "+3V3_456") (pintype "bidirectional"))
      (node (ref "R213") (pin "1") (pinfunction "1_1") (pintype "passive"))
    )
    (net (code "137") (name "Net-(LED214-+3V3)") (class "Default")
      (node (ref "LED214") (pin "456") (pinfunction "+3V3_456") (pintype "bidirectional"))
      (node (ref "R214") (pin "1") (pinfunction "1_1") (pintype "passive"))
    )
    (net (code "138") (name "Net-(LED215-+3V3)") (class "Default")
      (node (ref "LED215") (pin "456") (pinfunction "+3V3_456") (pintype "bidirectional"))
      (node (ref "R215") (pin "1") (pinfunction "1_1") (pintype "passive"))
    )
    (net (code "139") (name "Net-(LED216-+3V3)") (class "Default")
      (node (ref "LED216") (pin "456") (pinfunction "+3V3_456") (pintype "bidirectional"))
      (node (ref "R216") (pin "1") (pinfunction "1_1") (pintype "passive"))
    )
    (net (code "140") (name "S0") (class "Default")
      (node (ref "J2") (pin "2") (pinfunction "2_2") (pintype "bidirectional"))
      (node (ref "M0") (pin "10") (pinfunction "S0_10") (pintype "input"))
      (node (ref "M1") (pin "10") (pinfunction "S0_10") (pintype "input"))
      (node (ref "M2") (pin "10") (pinfunction "S0_10") (pintype "input"))
      (node (ref "M3") (pin "10") (pinfunction "S0_10") (pintype "input"))
      (node (ref "M4") (pin "10") (pinfunction "S0_10") (pintype "input"))
      (node (ref "M5") (pin "10") (pinfunction "S0_10") (pintype "input"))
    )
    (net (code "141") (name "S1") (class "Default")
      (node (ref "J2") (pin "4") (pinfunction "4_4") (pintype "bidirectional"))
      (node (ref "M0") (pin "11") (pinfunction "S1_11") (pintype "input"))
      (node (ref "M1") (pin "11") (pinfunction "S1_11") (pintype "input"))
      (node (ref "M2") (pin "11") (pinfunction "S1_11") (pintype "input"))
      (node (ref "M3") (pin "11") (pinfunction "S1_11") (pintype "input"))
      (node (ref "M4") (pin "11") (pinfunction "S1_11") (pintype "input"))
      (node (ref "M5") (pin "11") (pinfunction "S1_11") (pintype "input"))
    )
    (net (code "142") (name "S2") (class "Default")
      (node (ref "J1") (pin "2") (pinfunction "2_2") (pintype "bidirectional"))
      (node (ref "M0") (pin "14") (pinfunction "S2_14") (pintype "input"))
      (node (ref "M1") (pin "14") (pinfunction "S2_14") (pintype "input"))
      (node (ref "M2") (pin "14") (pinfunction "S2_14") (pintype "input"))
      (node (ref "M3") (pin "14") (pinfunction "S2_14") (pintype "input"))
      (node (ref "M4") (pin "14") (pinfunction "S2_14") (pintype "input"))
      (node (ref "M5") (pin "14") (pinfunction "S2_14") (pintype "input"))
    )
    (net (code "143") (name "S3") (class "Default")
      (node (ref "J1") (pin "1") (pinfunction "1_1") (pintype "bidirectional"))
      (node (ref "M0") (pin "13") (pinfunction "S3_13") (pintype "input"))
      (node (ref "M1") (pin "13") (pinfunction "S3_13") (pintype "input"))
      (node (ref "M2") (pin "13") (pinfunction "S3_13") (pintype "input"))
      (node (ref "M3") (pin "13") (pinfunction "S3_13") (pintype "input"))
      (node (ref "M4") (pin "13") (pinfunction "S3_13") (pintype "input"))
      (node (ref "M5") (pin "13") (pinfunction "S3_13") (pintype "input"))
    )
    (net (code "144") (name "SIGNAL_OUT_0") (class "Default")
      (node (ref "J1") (pin "3") (pinfunction "3_3") (pintype "bidirectional"))
      (node (ref "M0") (pin "1") (pinfunction "COM_1") (pintype "bidirectional"))
    )
    (net (code "145") (name "SIGNAL_OUT_1") (class "Default")
      (node (ref "J2") (pin "1") (pinfunction "1_1") (pintype "bidirectional"))
      (node (ref "M1") (pin "1") (pinfunction "COM_1") (pintype "bidirectional"))
    )
    (net (code "146") (name "SIGNAL_OUT_2") (class "Default")
      (node (ref "J1") (pin "4") (pinfunction "4_4") (pintype "bidirectional"))
      (node (ref "M2") (pin "1") (pinfunction "COM_1") (pintype "bidirectional"))
    )
    (net (code "147") (name "SIGNAL_OUT_3") (class "Default")
      (node (ref "J2") (pin "3") (pinfunction "3_3") (pintype "bidirectional"))
      (node (ref "M3") (pin "1") (pinfunction "COM_1") (pintype "bidirectional"))
    )
    (net (code "148") (name "SIGNAL_OUT_4") (class "Default")
      (node (ref "J1") (pin "5") (pinfunction "5_5") (pintype "bidirectional"))
      (node (ref "M4") (pin "1") (pinfunction "COM_1") (pintype "bidirectional"))
    )
    (net (code "149") (name "SIGNAL_OUT_5") (class "Default")
      (node (ref "J2") (pin "5") (pinfunction "5_5") (pintype "bidirectional"))
      (node (ref "M5") (pin "1") (pinfunction "COM_1") (pintype "bidirectional"))
    )
    (net (code "150") (name "unconnected-(J1-PadMP1)") (class "Default")
      (node (ref "J1") (pin "MP1") (pinfunction "MP1_MP1") (pintype "no_connect"))
    )
    (net (code "151") (name "unconnected-(J1-PadMP2)") (class "Default")
      (node (ref "J1") (pin "MP2") (pinfunction "MP2_MP2") (pintype "no_connect"))
    )
    (net (code "152") (name "unconnected-(J2-PadMP1)") (class "Default")
      (node (ref "J2") (pin "MP1") (pinfunction "MP1_MP1") (pintype "no_connect"))
    )
    (net (code "153") (name "unconnected-(J2-PadMP2)") (class "Default")
      (node (ref "J2") (pin "MP2") (pinfunction "MP2_MP2") (pintype "no_connect"))
    )
  )
)
